# 8_bit_Left_Rev_A.net
KiCad netlist of a schematic drawn in EAGLE
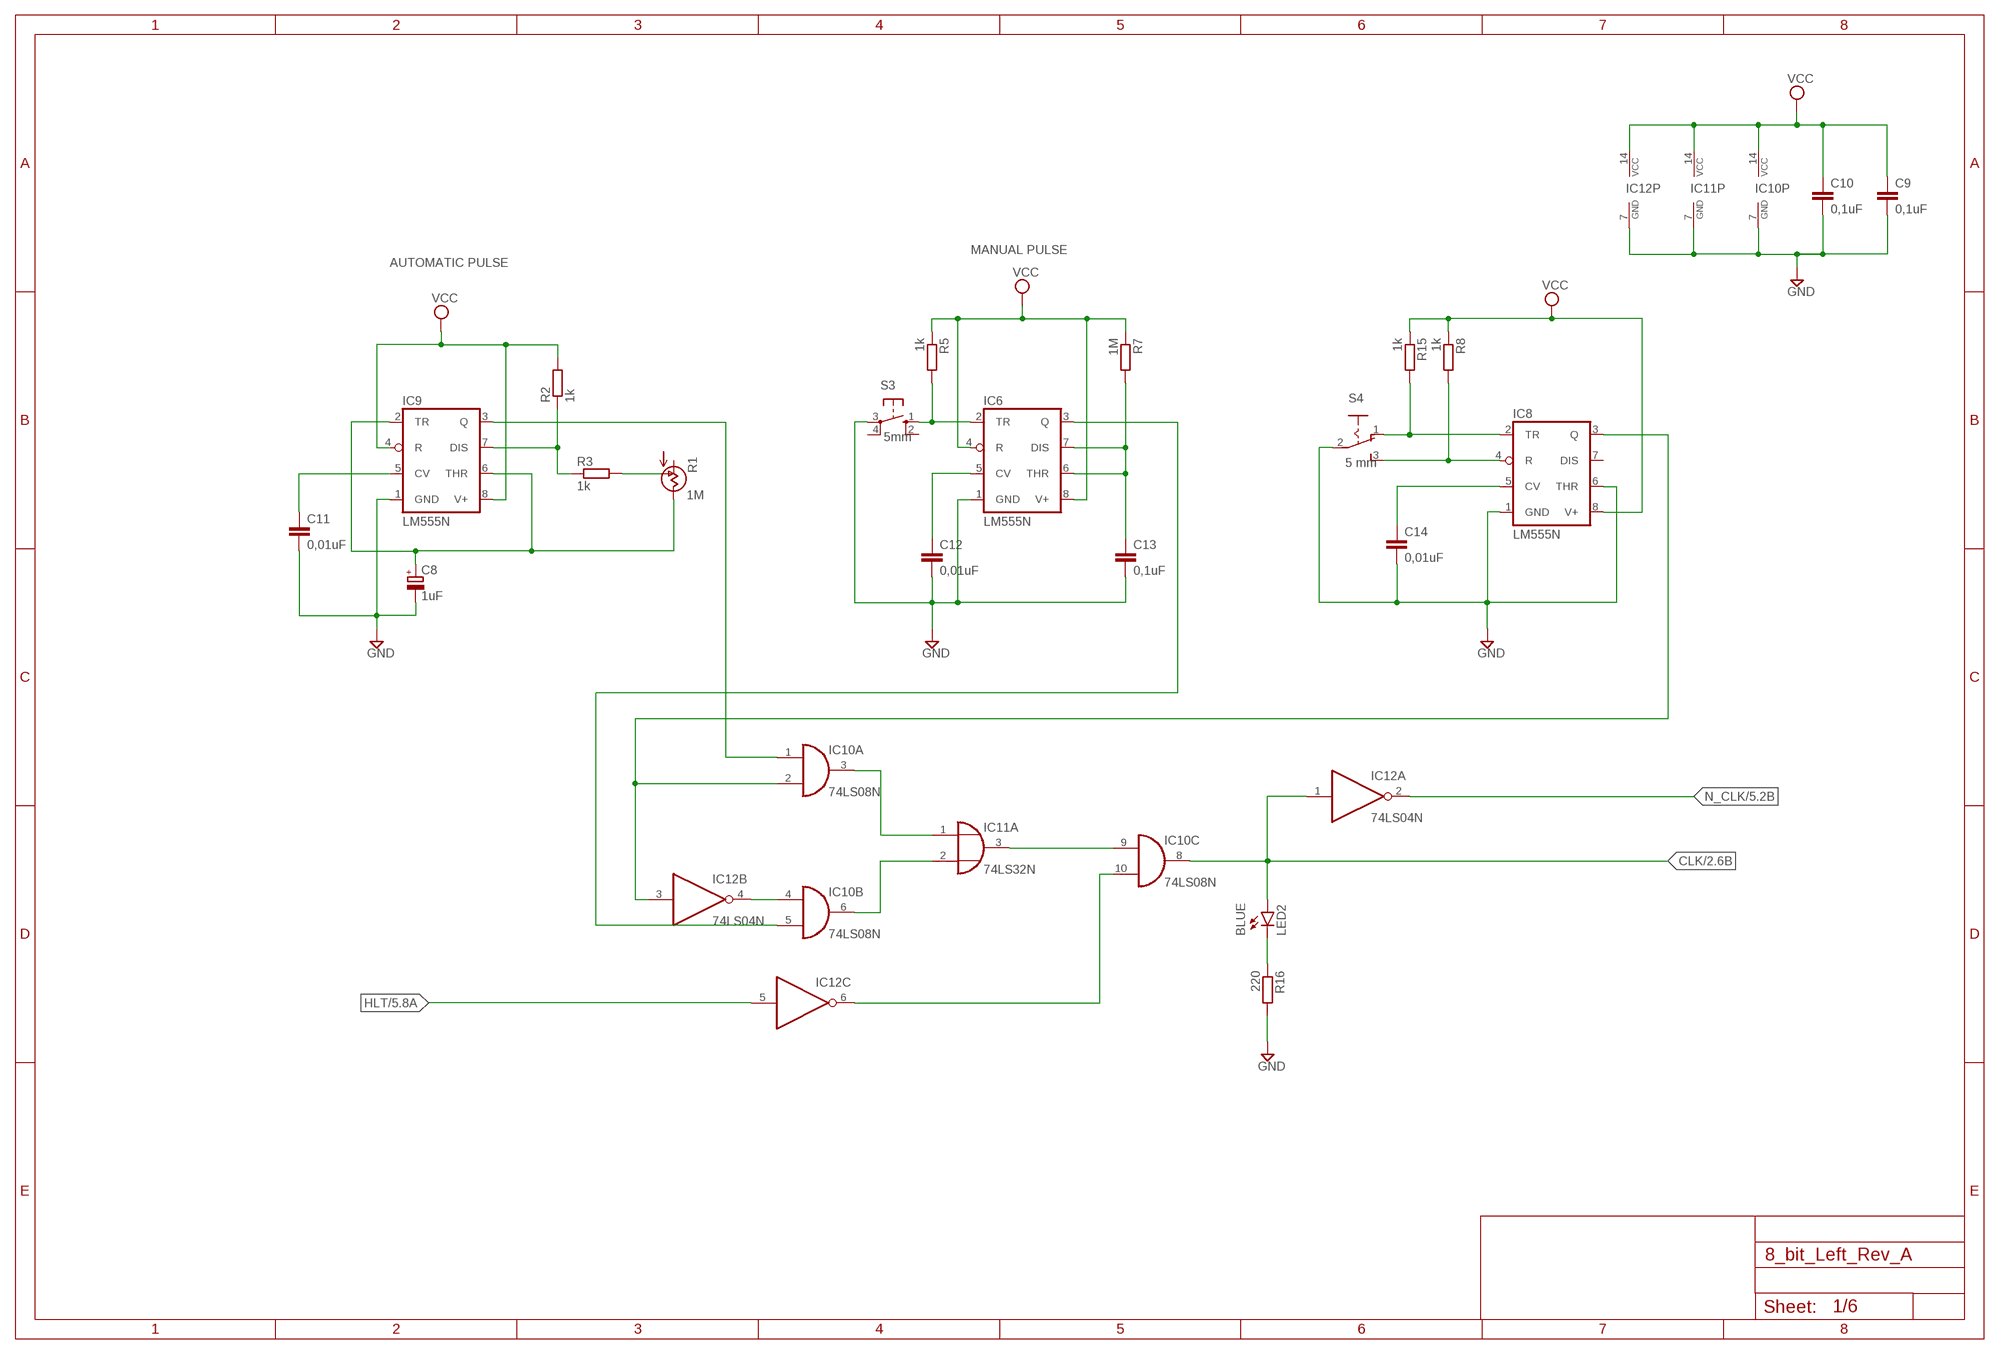
[diagram p0: schematic, sheet 1]
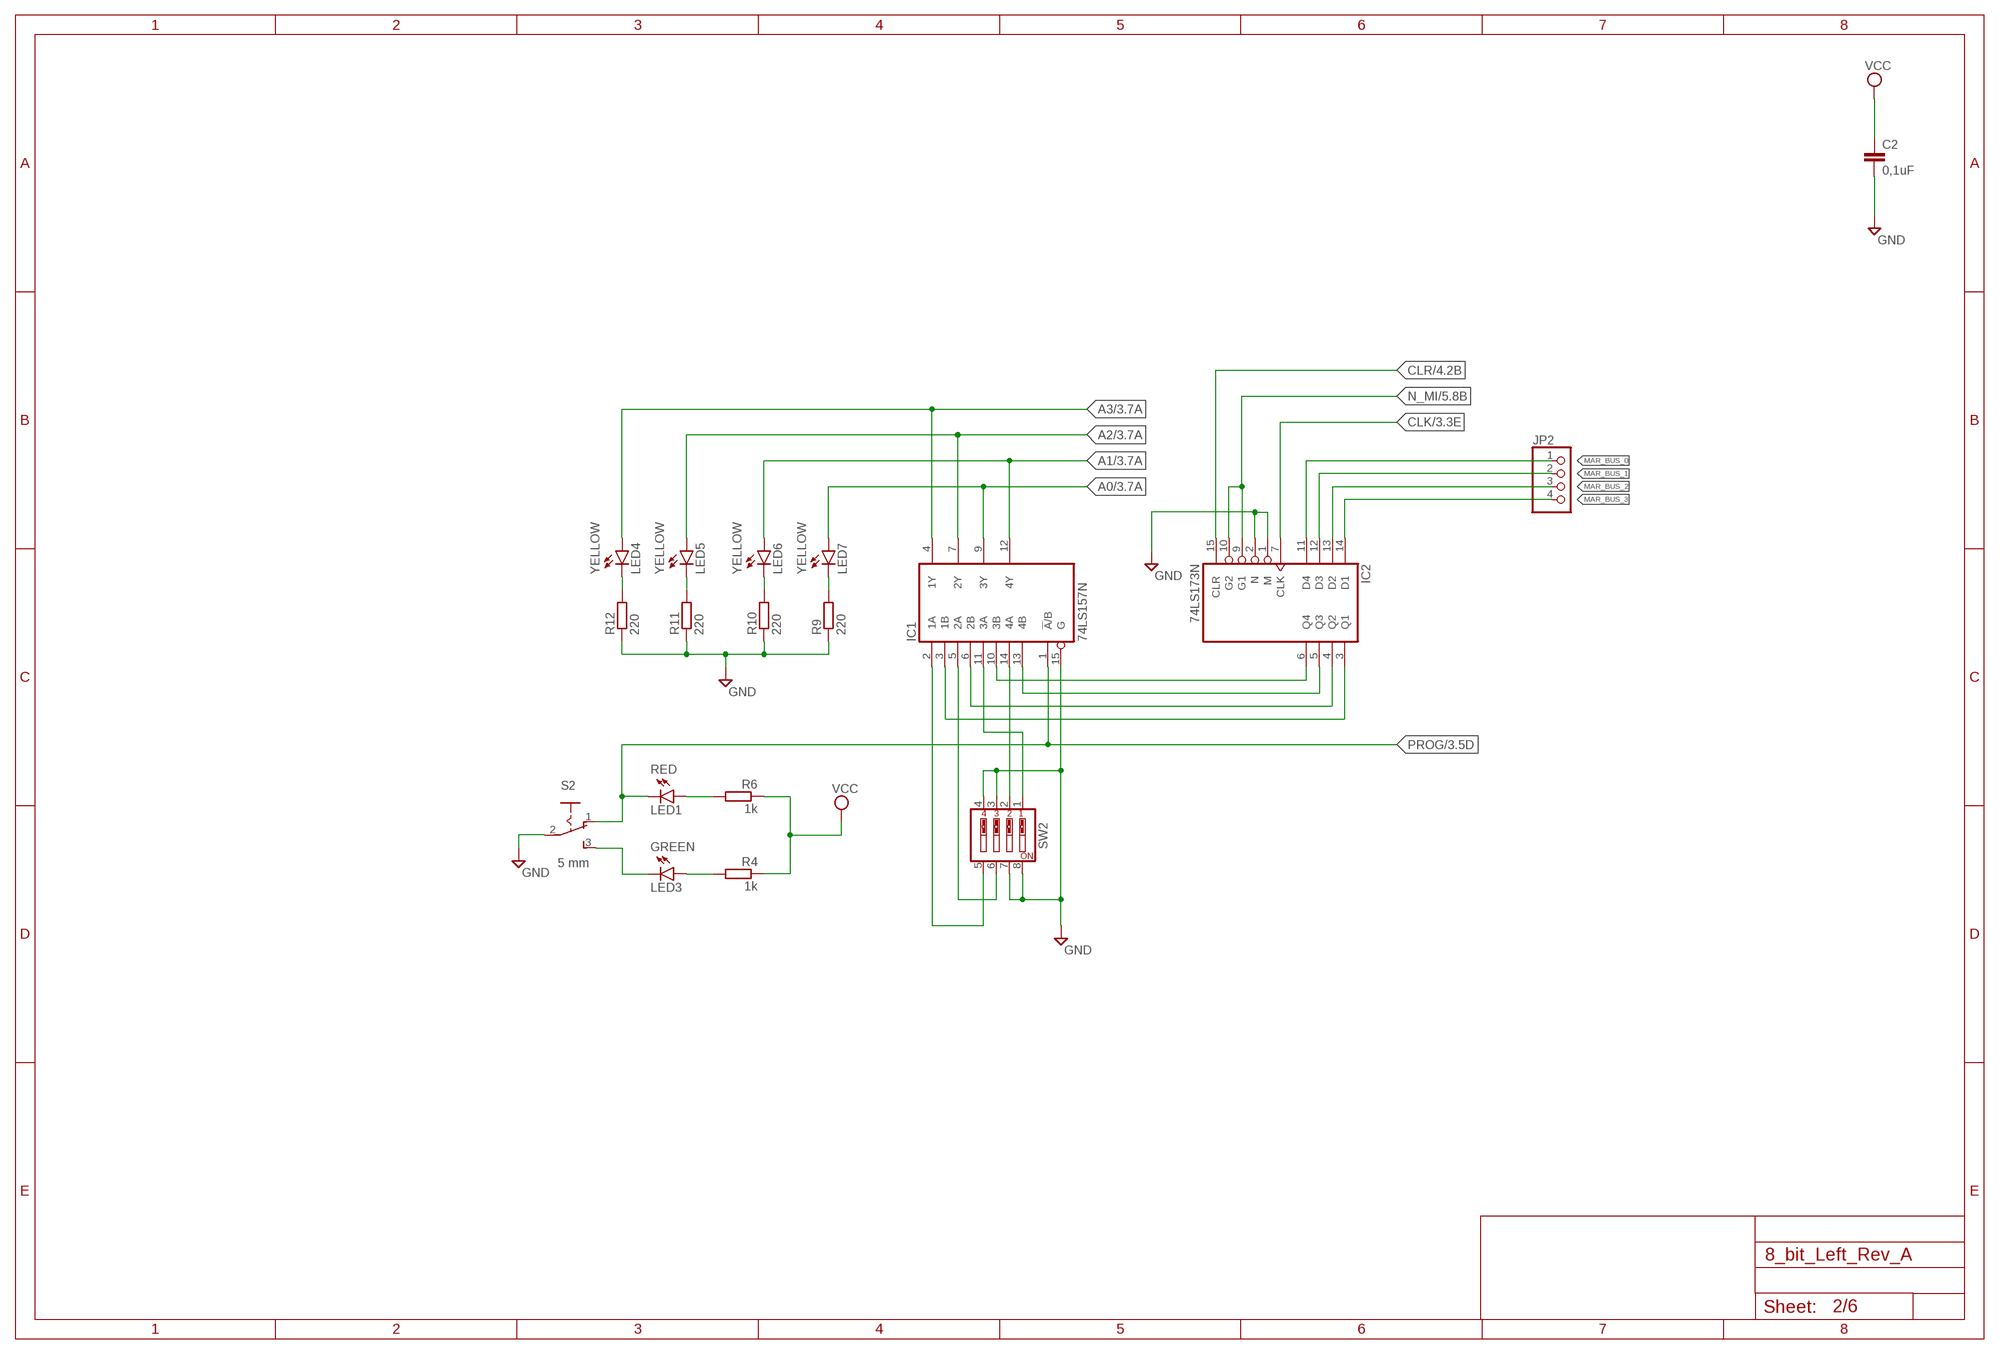
[diagram p1: schematic, sheet 2]
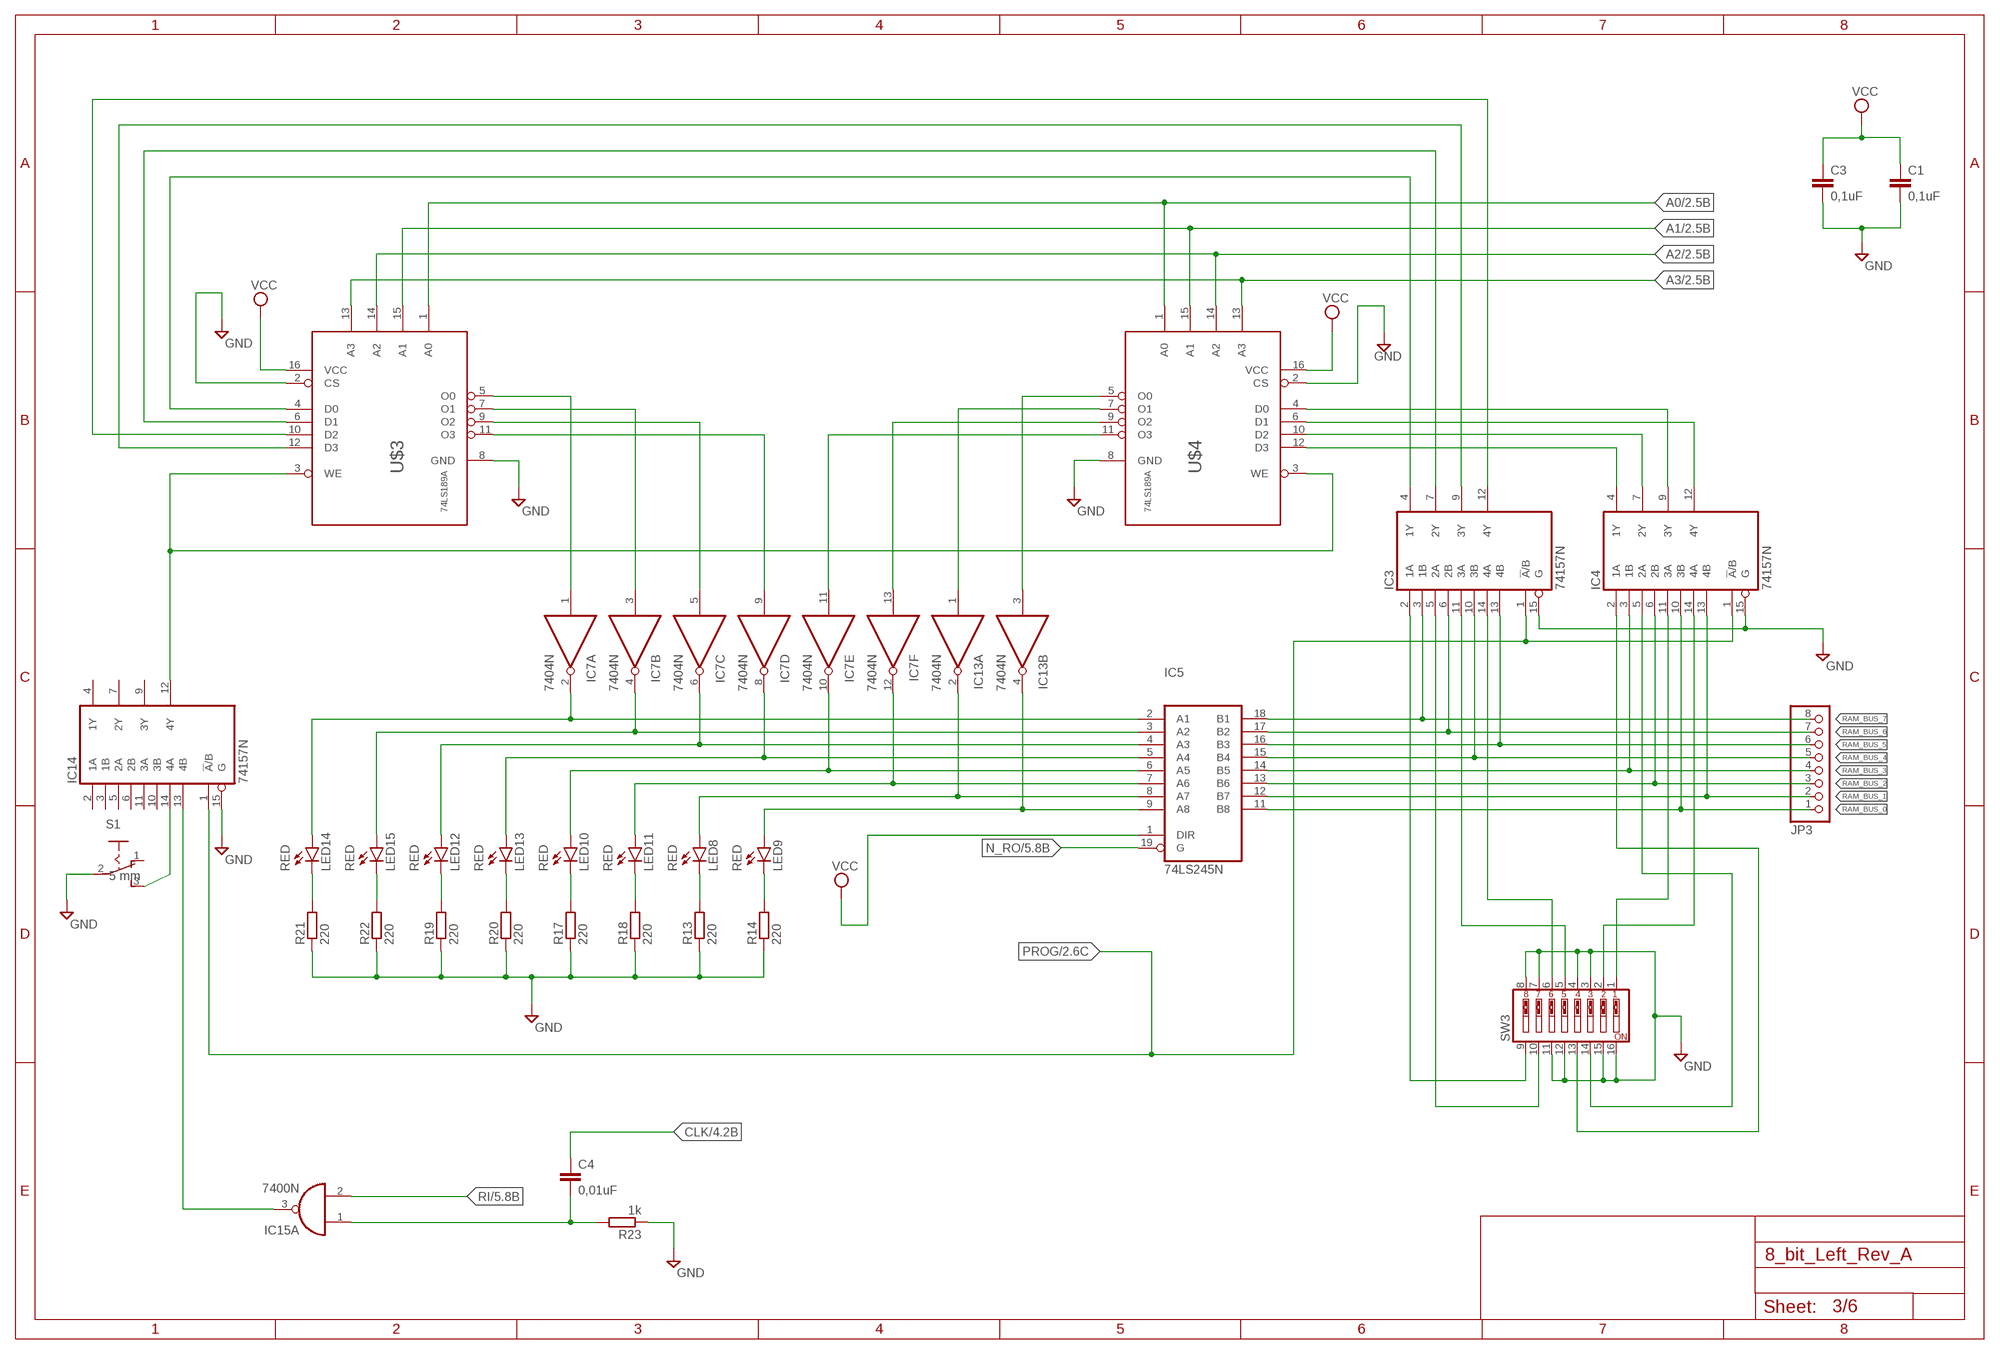
[diagram p2: schematic, sheet 3]
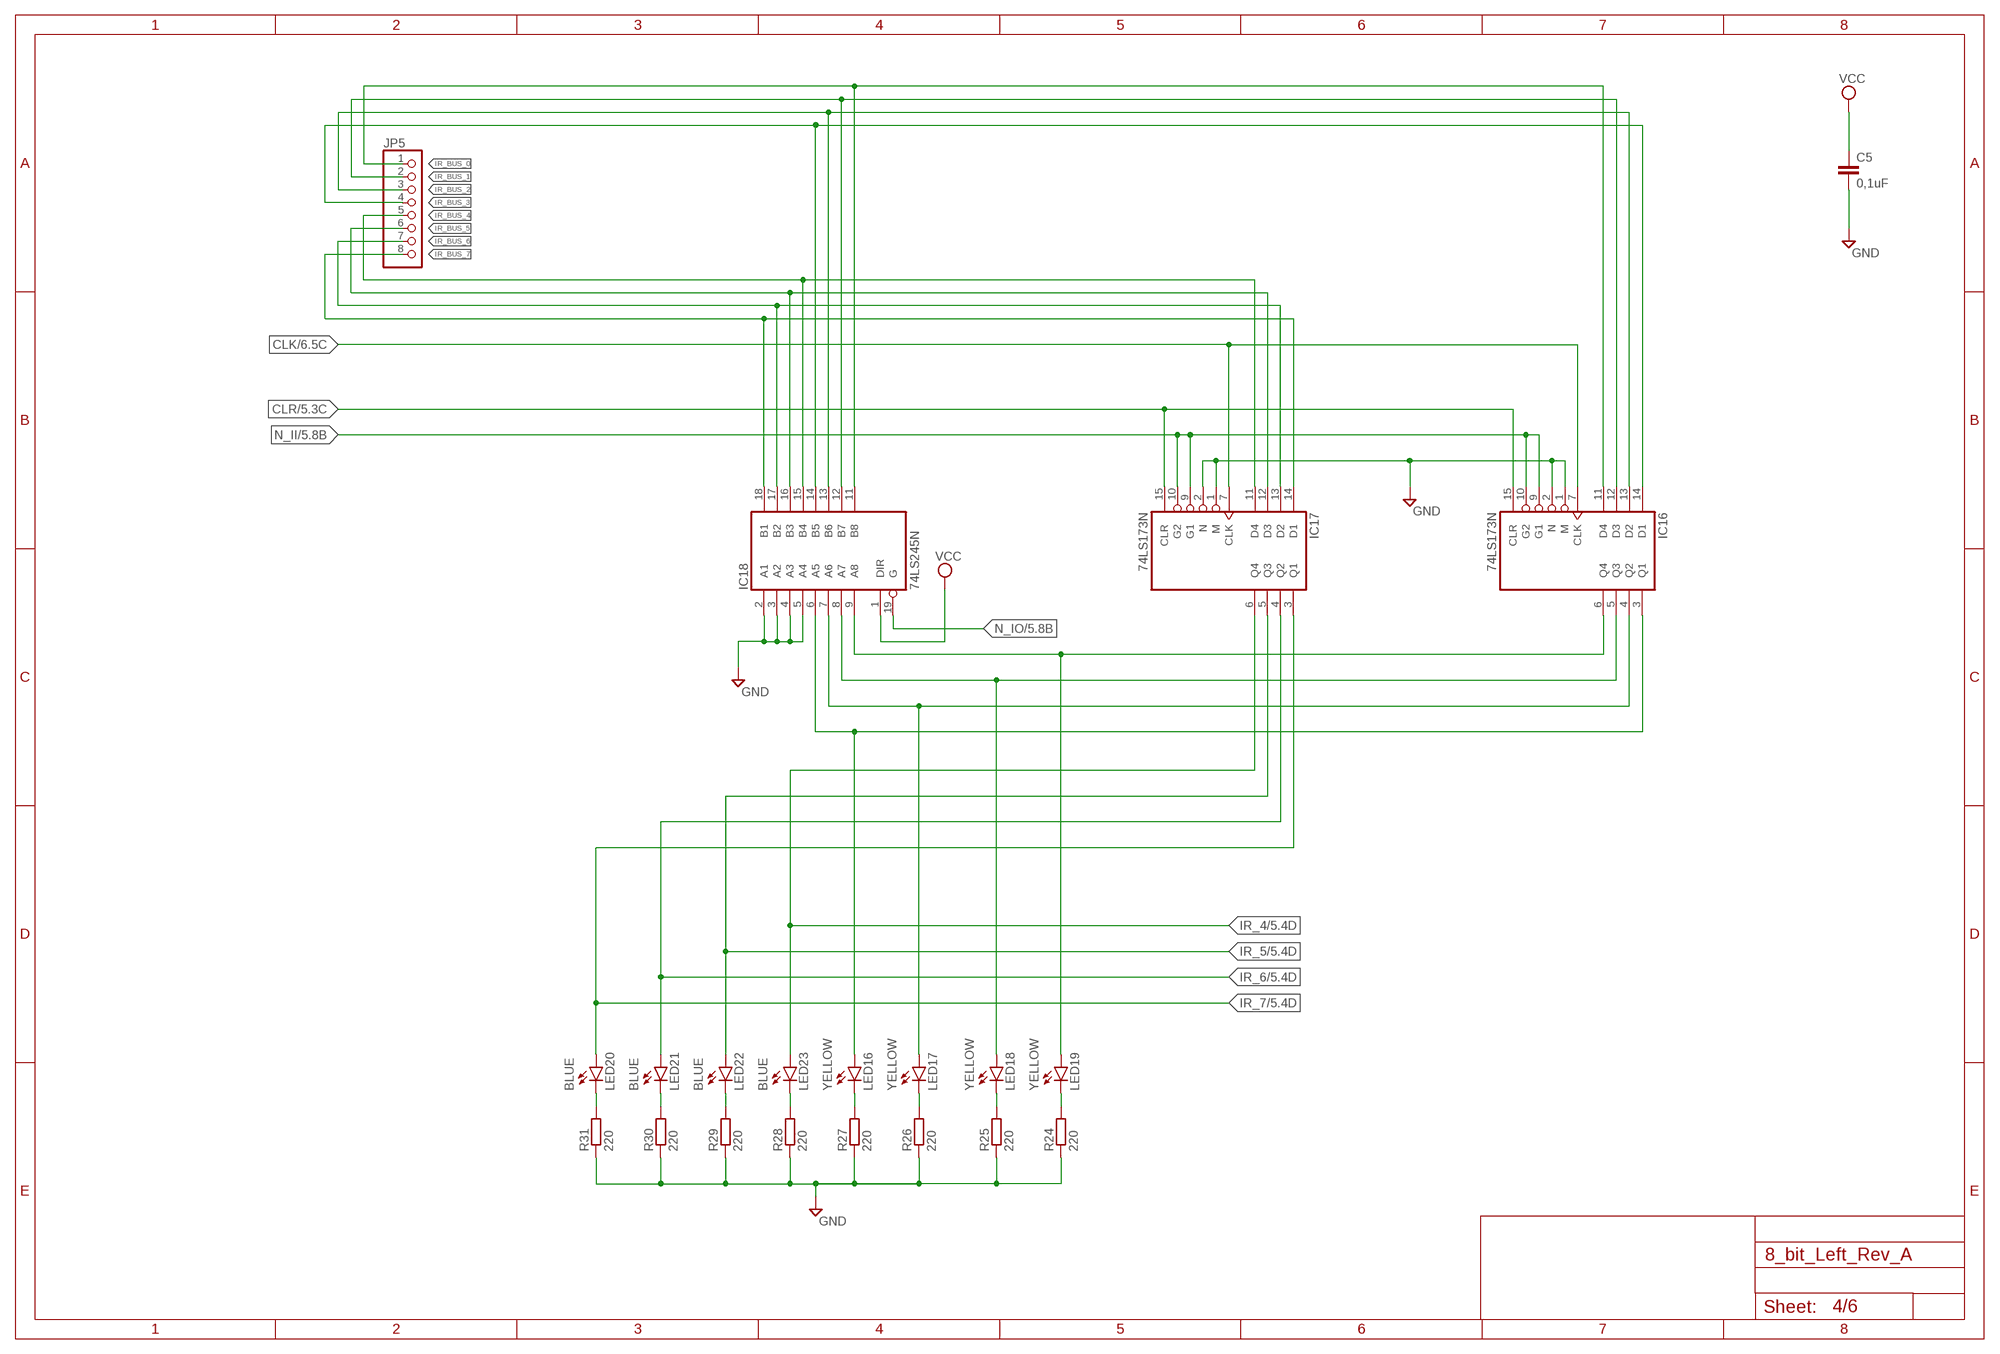
[diagram p3: schematic, sheet 4]
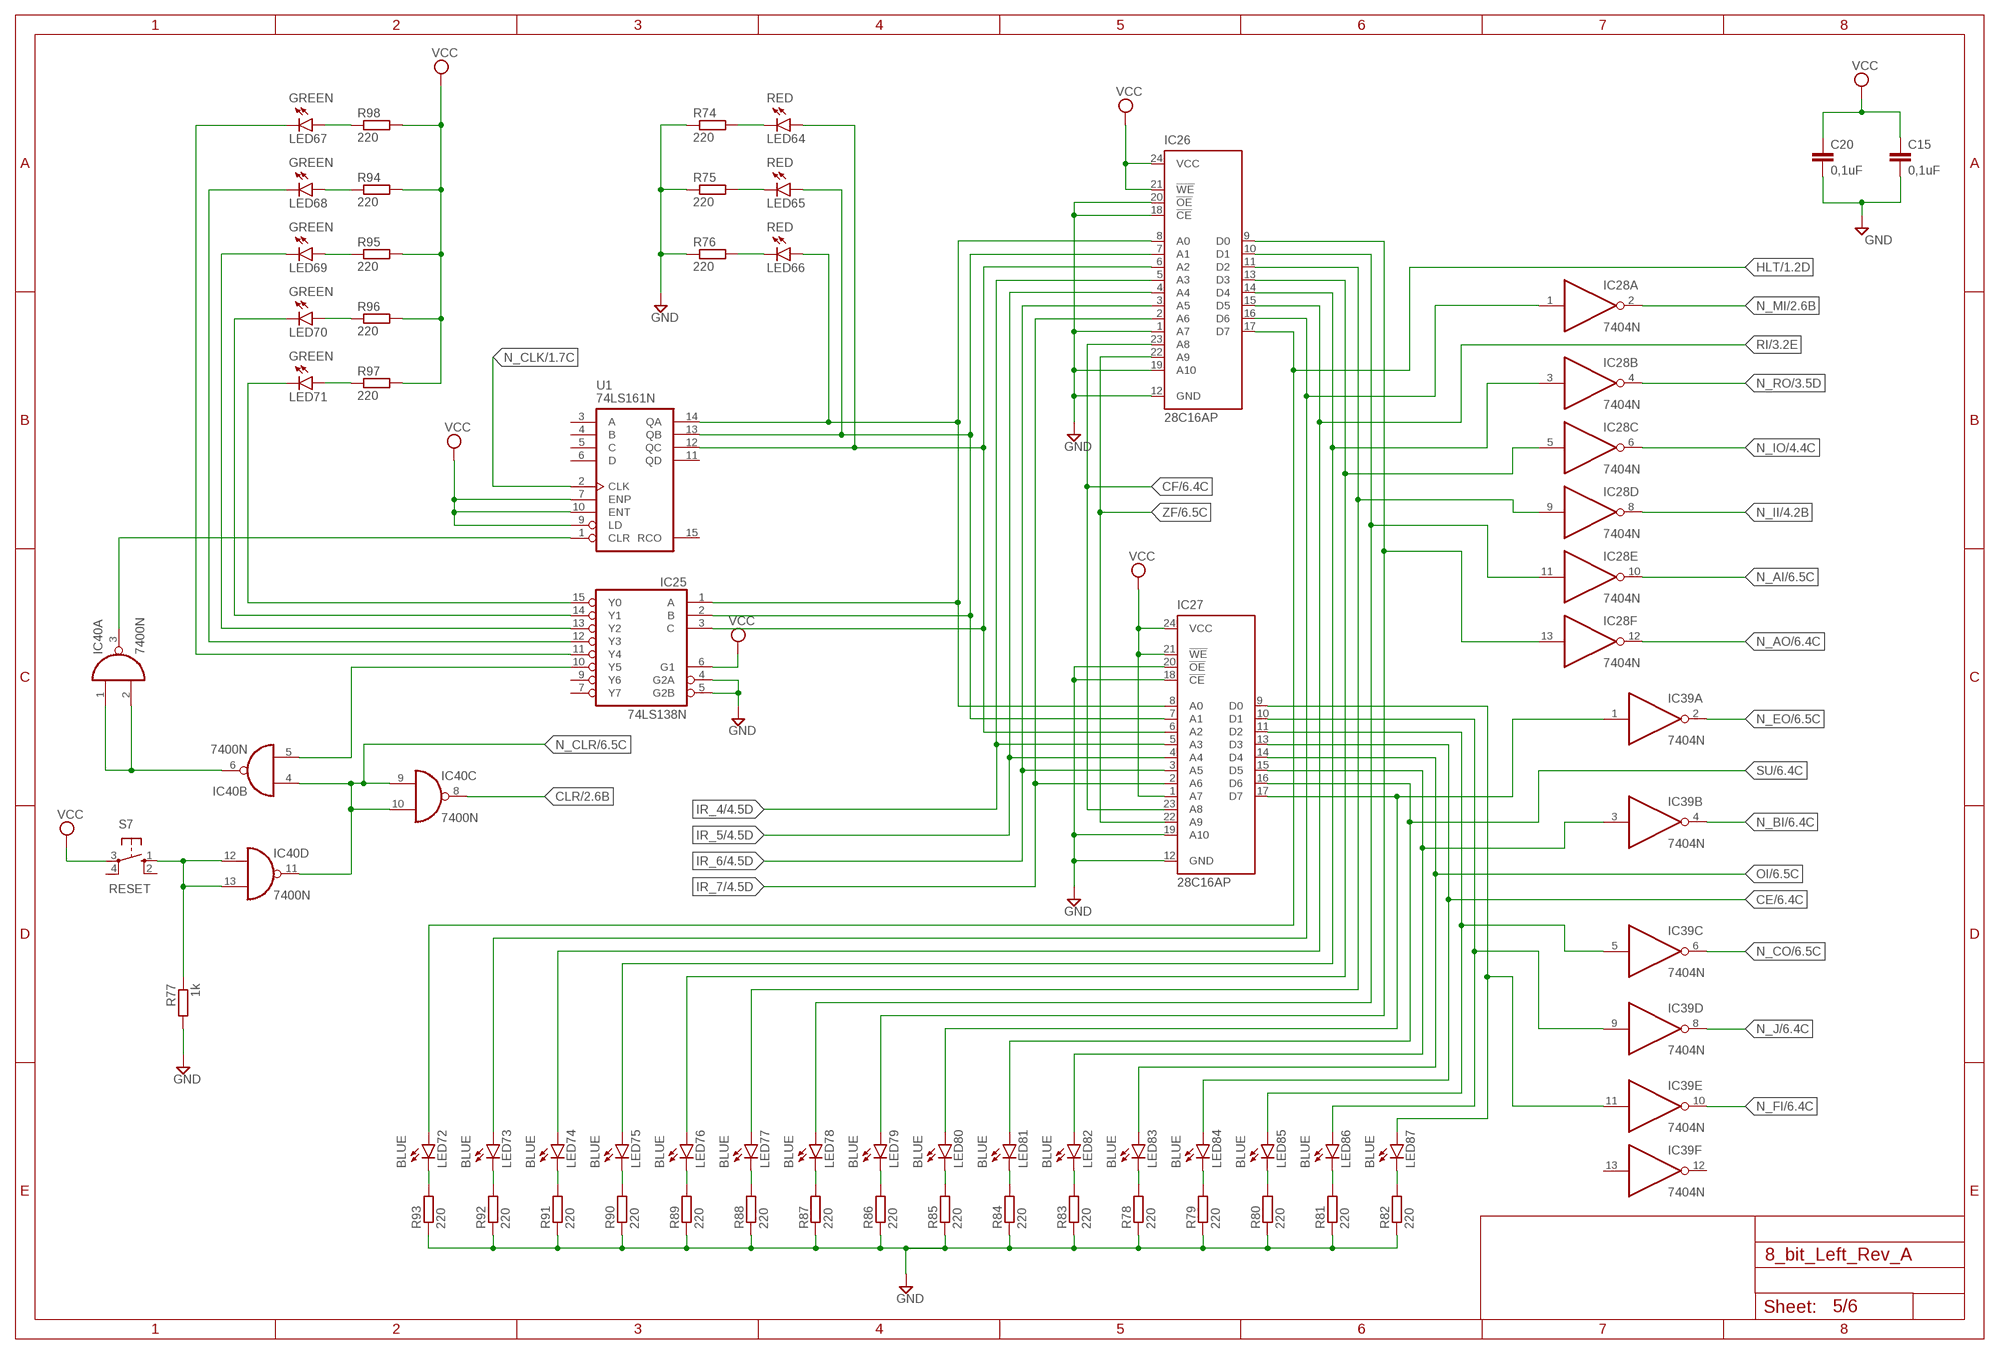
[diagram p4: schematic, sheet 5]
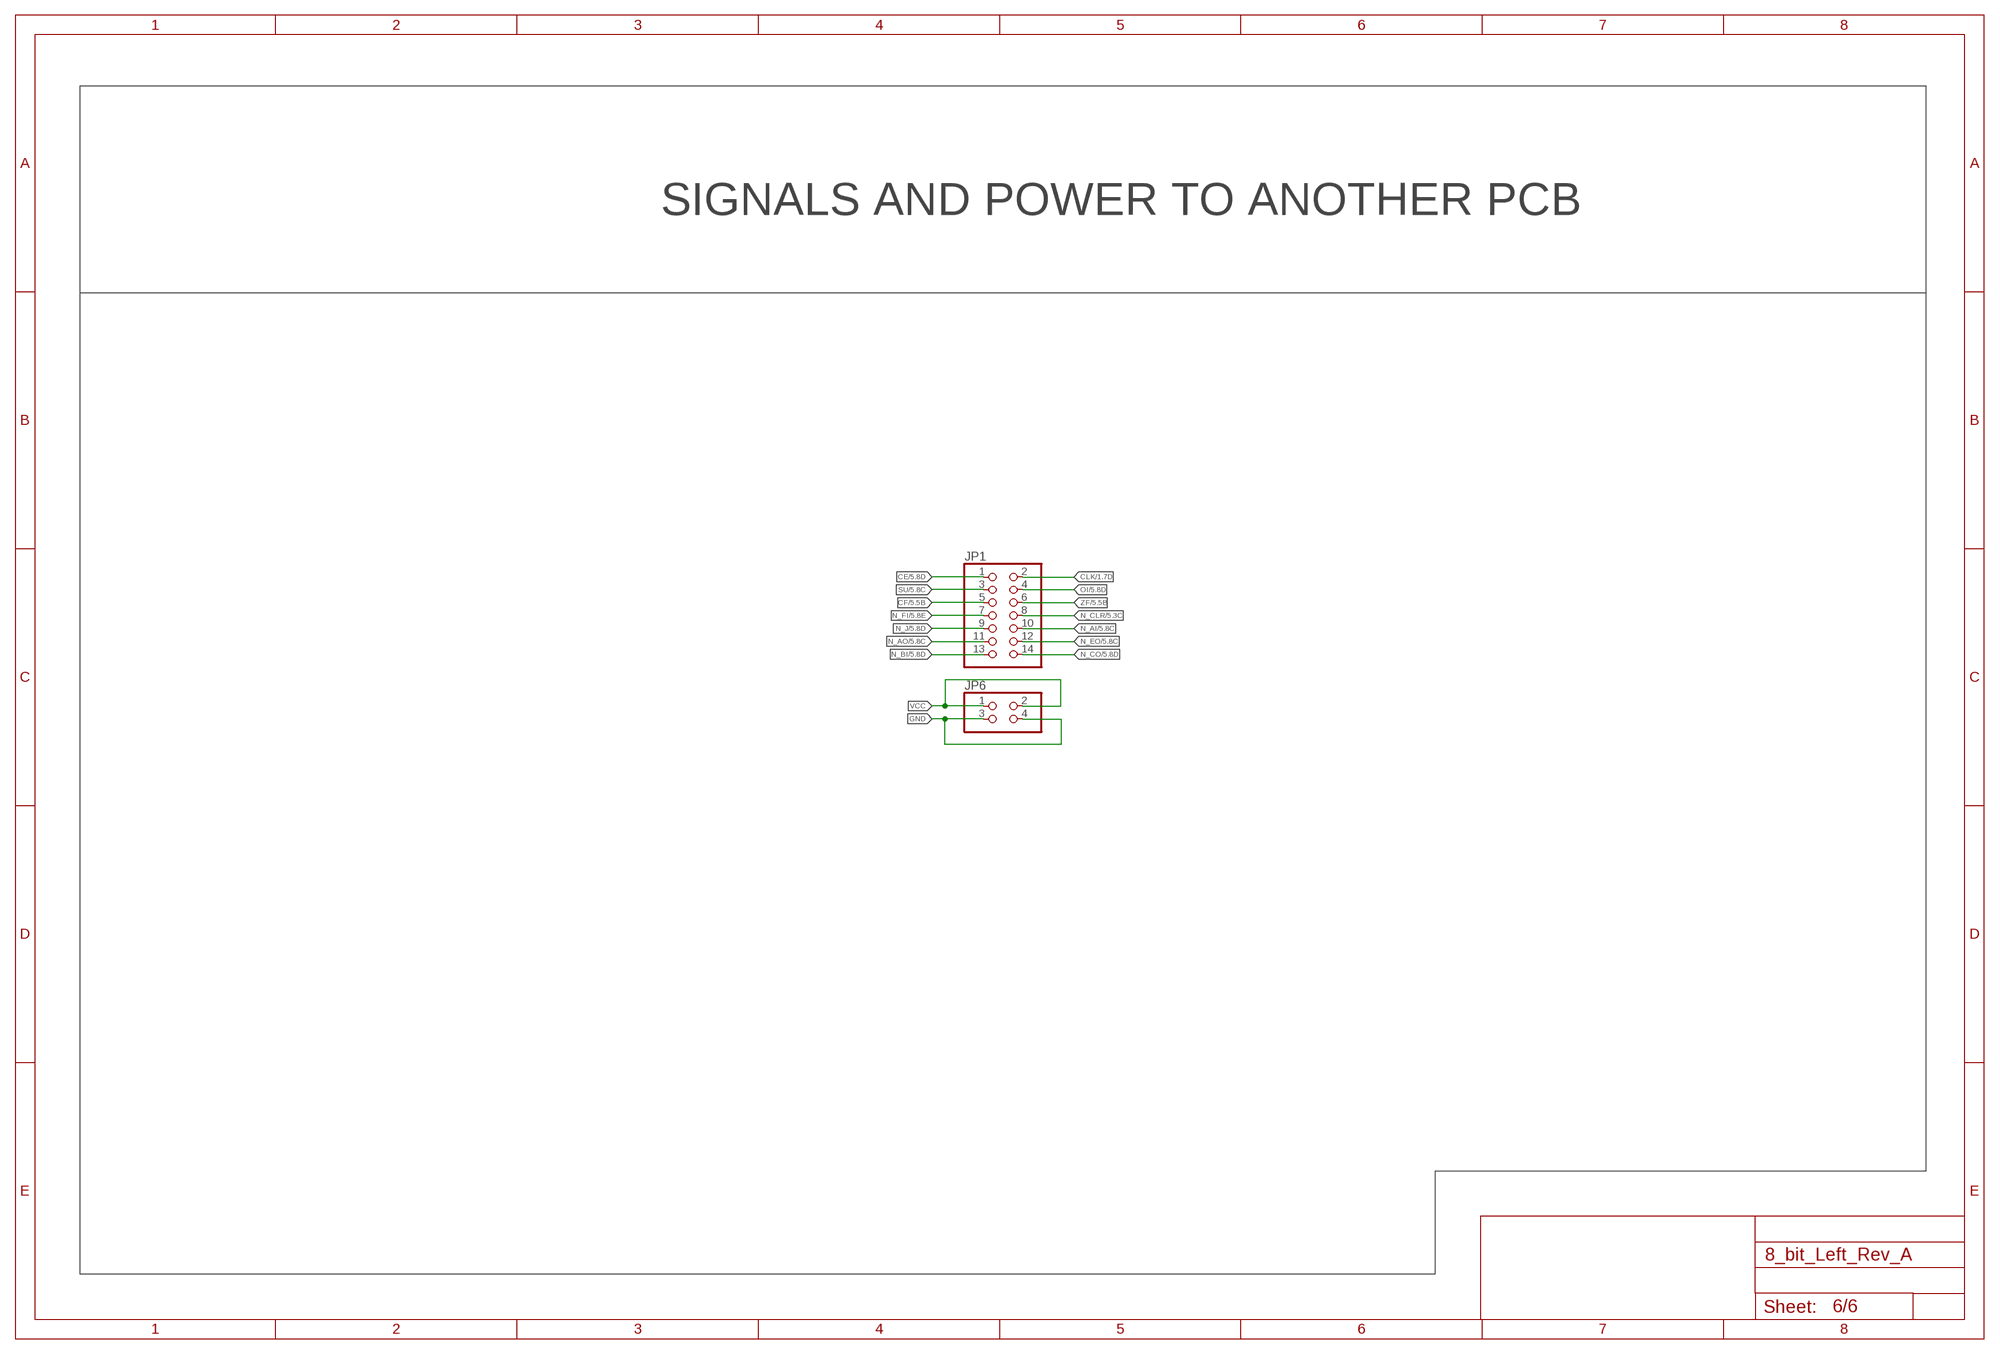
[diagram p5: schematic, sheet 6]

(export (version "E")
  (design (tool "Eeschema 10.0.6"))
  (components
    (comp (ref "C8")
      (value "1uF")
      (footprint "eagle-import:E2-5")
      (libsource (lib "eagle-import") (part "CPOL-EUE2-5"))
    )
    (comp (ref "C9")
      (value "0,1uF")
      (footprint "eagle-import:C025-030X050")
      (libsource (lib "eagle-import") (part "C-EU025-030X050"))
    )
    (comp (ref "C10")
      (value "0,1uF")
      (footprint "eagle-import:C025-030X050")
      (libsource (lib "eagle-import") (part "C-EU025-030X050"))
    )
    (comp (ref "C11")
      (value "0,01uF")
      (footprint "eagle-import:C025-030X050")
      (libsource (lib "eagle-import") (part "C-EU025-030X050"))
    )
    (comp (ref "C12")
      (value "0,01uF")
      (footprint "eagle-import:C025-030X050")
      (libsource (lib "eagle-import") (part "C-EU025-030X050"))
    )
    (comp (ref "C13")
      (value "0,1uF")
      (footprint "eagle-import:C025-030X050")
      (libsource (lib "eagle-import") (part "C-EU025-030X050"))
    )
    (comp (ref "C14")
      (value "0,01uF")
      (footprint "eagle-import:C025-030X050")
      (libsource (lib "eagle-import") (part "C-EU025-030X050"))
    )
    (comp (ref "IC6")
      (value "LM555N")
      (footprint "eagle-import:DIL08")
      (libsource (lib "eagle-import") (part "555NLM"))
    )
    (comp (ref "IC8")
      (value "LM555N")
      (footprint "eagle-import:DIL08")
      (libsource (lib "eagle-import") (part "555NLM"))
    )
    (comp (ref "IC9")
      (value "LM555N")
      (footprint "eagle-import:DIL08")
      (libsource (lib "eagle-import") (part "555NLM"))
    )
    (comp (ref "IC10")
      (value "74LS08N")
      (footprint "eagle-import:DIL14")
      (libsource (lib "eagle-import") (part "7408NLS"))
    )
    (comp (ref "IC11")
      (value "74LS32N")
      (footprint "eagle-import:DIL14")
      (libsource (lib "eagle-import") (part "7432NLS"))
    )
    (comp (ref "IC12")
      (value "74LS04N")
      (footprint "eagle-import:DIL14")
      (libsource (lib "eagle-import") (part "7404NLS"))
    )
    (comp (ref "LED2")
      (value "BLUE")
      (footprint "eagle-import:LED5MM")
      (libsource (lib "eagle-import") (part "LED5MM"))
    )
    (comp (ref "R1")
      (value "1M")
      (footprint "eagle-import:S64W")
      (fields (field (name "R9") "1M"))
      (libsource (lib "eagle-import") (part "POTTRS64W"))
    )
    (comp (ref "R2")
      (value "1k")
      (footprint "eagle-import:0207_10")
      (libsource (lib "eagle-import") (part "R-EU_0207/10"))
    )
    (comp (ref "R3")
      (value "1k")
      (footprint "eagle-import:0207_10")
      (libsource (lib "eagle-import") (part "R-EU_0207/10"))
    )
    (comp (ref "R5")
      (value "1k")
      (footprint "eagle-import:0207_10")
      (libsource (lib "eagle-import") (part "R-EU_0207/10"))
    )
    (comp (ref "R7")
      (value "1M")
      (footprint "eagle-import:0207_10")
      (libsource (lib "eagle-import") (part "R-EU_0207/10"))
    )
    (comp (ref "R8")
      (value "1k")
      (footprint "eagle-import:0207_10")
      (libsource (lib "eagle-import") (part "R-EU_0207/10"))
    )
    (comp (ref "R15")
      (value "1k")
      (footprint "eagle-import:0207_10")
      (libsource (lib "eagle-import") (part "R-EU_0207/10"))
    )
    (comp (ref "R16")
      (value "220")
      (footprint "eagle-import:0207_10")
      (libsource (lib "eagle-import") (part "R-EU_0207/10"))
    )
    (comp (ref "S3")
      (value "5mm")
      (footprint "eagle-import:B3F-10XX")
      (fields (field (name "MPN") "B3F-1000"))
      (libsource (lib "eagle-import") (part "10-XX"))
    )
    (comp (ref "S4")
      (value "5 mm")
      (footprint "eagle-import:255SB")
      (libsource (lib "eagle-import") (part "255SB"))
    )
    (comp (ref "C1")
      (value "0,1uF")
      (footprint "eagle-import:C025-030X050")
      (libsource (lib "eagle-import") (part "C-EU025-030X050"))
    )
    (comp (ref "C3")
      (value "0,1uF")
      (footprint "eagle-import:C025-030X050")
      (libsource (lib "eagle-import") (part "C-EU025-030X050"))
    )
    (comp (ref "C4")
      (value "0,01uF")
      (footprint "eagle-import:C025-030X050")
      (libsource (lib "eagle-import") (part "C-EU025-030X050"))
    )
    (comp (ref "IC3")
      (value "74157N")
      (footprint "eagle-import:DIL16")
      (libsource (lib "eagle-import") (part "74xx-eu_85_74157N"))
    )
    (comp (ref "IC4")
      (value "74157N")
      (footprint "eagle-import:DIL16")
      (libsource (lib "eagle-import") (part "74xx-eu_85_74157N"))
    )
    (comp (ref "IC5")
      (value "74LS245N")
      (footprint "eagle-import:DIL20")
      (libsource (lib "eagle-import") (part "74245NLS"))
    )
    (comp (ref "IC7")
      (value "7404N")
      (footprint "eagle-import:DIL14")
      (libsource (lib "eagle-import") (part "7404N"))
    )
    (comp (ref "IC13")
      (value "7404N")
      (footprint "eagle-import:DIL14")
      (libsource (lib "eagle-import") (part "7404N"))
    )
    (comp (ref "IC14")
      (value "74157N")
      (footprint "eagle-import:DIL16")
      (libsource (lib "eagle-import") (part "74xx-eu_85_74157N"))
    )
    (comp (ref "IC15")
      (value "7400N")
      (footprint "eagle-import:DIL14")
      (libsource (lib "eagle-import") (part "7400N"))
    )
    (comp (ref "JP3")
      (value "PINHD-1X8")
      (footprint "eagle-import:1X08")
      (libsource (lib "eagle-import") (part "PINHD-1X8"))
    )
    (comp (ref "LED8")
      (value "RED")
      (footprint "eagle-import:LED5MM")
      (libsource (lib "eagle-import") (part "LED5MM"))
    )
    (comp (ref "LED9")
      (value "RED")
      (footprint "eagle-import:LED5MM")
      (libsource (lib "eagle-import") (part "LED5MM"))
    )
    (comp (ref "LED10")
      (value "RED")
      (footprint "eagle-import:LED5MM")
      (libsource (lib "eagle-import") (part "LED5MM"))
    )
    (comp (ref "LED11")
      (value "RED")
      (footprint "eagle-import:LED5MM")
      (libsource (lib "eagle-import") (part "LED5MM"))
    )
    (comp (ref "LED12")
      (value "RED")
      (footprint "eagle-import:LED5MM")
      (libsource (lib "eagle-import") (part "LED5MM"))
    )
    (comp (ref "LED13")
      (value "RED")
      (footprint "eagle-import:LED5MM")
      (libsource (lib "eagle-import") (part "LED5MM"))
    )
    (comp (ref "LED14")
      (value "RED")
      (footprint "eagle-import:LED5MM")
      (libsource (lib "eagle-import") (part "LED5MM"))
    )
    (comp (ref "LED15")
      (value "RED")
      (footprint "eagle-import:LED5MM")
      (libsource (lib "eagle-import") (part "LED5MM"))
    )
    (comp (ref "R13")
      (value "220")
      (footprint "eagle-import:0207_10")
      (libsource (lib "eagle-import") (part "R-EU_0207/10"))
    )
    (comp (ref "R14")
      (value "220")
      (footprint "eagle-import:0207_10")
      (libsource (lib "eagle-import") (part "R-EU_0207/10"))
    )
    (comp (ref "R17")
      (value "220")
      (footprint "eagle-import:0207_10")
      (libsource (lib "eagle-import") (part "R-EU_0207/10"))
    )
    (comp (ref "R18")
      (value "220")
      (footprint "eagle-import:0207_10")
      (libsource (lib "eagle-import") (part "R-EU_0207/10"))
    )
    (comp (ref "R19")
      (value "220")
      (footprint "eagle-import:0207_10")
      (libsource (lib "eagle-import") (part "R-EU_0207/10"))
    )
    (comp (ref "R20")
      (value "220")
      (footprint "eagle-import:0207_10")
      (libsource (lib "eagle-import") (part "R-EU_0207/10"))
    )
    (comp (ref "R21")
      (value "220")
      (footprint "eagle-import:0207_10")
      (libsource (lib "eagle-import") (part "R-EU_0207/10"))
    )
    (comp (ref "R22")
      (value "220")
      (footprint "eagle-import:0207_10")
      (libsource (lib "eagle-import") (part "R-EU_0207/10"))
    )
    (comp (ref "R23")
      (value "1k")
      (footprint "eagle-import:0207_10")
      (libsource (lib "eagle-import") (part "R-EU_0207/10"))
    )
    (comp (ref "S1")
      (value "5 mm")
      (footprint "eagle-import:255SB")
      (libsource (lib "eagle-import") (part "255SB"))
    )
    (comp (ref "SW3")
      (value "SW_DIP-8")
      (footprint "eagle-import:EDG-08")
      (libsource (lib "eagle-import") (part "SW_DIP-8"))
    )
    (comp (ref "U$3")
      (value "74LS189A")
      (footprint "eagle-import:74LS189")
      (libsource (lib "eagle-import") (part "74LS189A"))
    )
    (comp (ref "U$4")
      (value "74LS189A")
      (footprint "eagle-import:74LS189")
      (libsource (lib "eagle-import") (part "74LS189A"))
    )
    (comp (ref "C2")
      (value "0,1uF")
      (footprint "eagle-import:C025-030X050")
      (libsource (lib "eagle-import") (part "C-EU025-030X050"))
    )
    (comp (ref "IC1")
      (value "74LS157N")
      (footprint "eagle-import:DIL16")
      (libsource (lib "eagle-import") (part "74157NLS"))
    )
    (comp (ref "IC2")
      (value "74LS173N")
      (footprint "eagle-import:DIL16")
      (libsource (lib "eagle-import") (part "74173NLS"))
    )
    (comp (ref "JP2")
      (value "PINHD-1X4")
      (footprint "eagle-import:1X04")
      (libsource (lib "eagle-import") (part "PINHD-1X4"))
    )
    (comp (ref "LED1")
      (value "RED")
      (footprint "eagle-import:LED5MM")
      (libsource (lib "eagle-import") (part "LED5MM"))
    )
    (comp (ref "LED3")
      (value "GREEN")
      (footprint "eagle-import:LED5MM")
      (libsource (lib "eagle-import") (part "LED5MM"))
    )
    (comp (ref "LED4")
      (value "YELLOW")
      (footprint "eagle-import:LED5MM")
      (libsource (lib "eagle-import") (part "LED5MM"))
    )
    (comp (ref "LED5")
      (value "YELLOW")
      (footprint "eagle-import:LED5MM")
      (libsource (lib "eagle-import") (part "LED5MM"))
    )
    (comp (ref "LED6")
      (value "YELLOW")
      (footprint "eagle-import:LED5MM")
      (libsource (lib "eagle-import") (part "LED5MM"))
    )
    (comp (ref "LED7")
      (value "YELLOW")
      (footprint "eagle-import:LED5MM")
      (libsource (lib "eagle-import") (part "LED5MM"))
    )
    (comp (ref "R4")
      (value "1k")
      (footprint "eagle-import:0207_10")
      (libsource (lib "eagle-import") (part "R-EU_0207/10"))
    )
    (comp (ref "R6")
      (value "1k")
      (footprint "eagle-import:0207_10")
      (libsource (lib "eagle-import") (part "R-EU_0207/10"))
    )
    (comp (ref "R9")
      (value "220")
      (footprint "eagle-import:0207_10")
      (libsource (lib "eagle-import") (part "R-EU_0207/10"))
    )
    (comp (ref "R10")
      (value "220")
      (footprint "eagle-import:0207_10")
      (libsource (lib "eagle-import") (part "R-EU_0207/10"))
    )
    (comp (ref "R11")
      (value "220")
      (footprint "eagle-import:0207_10")
      (libsource (lib "eagle-import") (part "R-EU_0207/10"))
    )
    (comp (ref "R12")
      (value "220")
      (footprint "eagle-import:0207_10")
      (libsource (lib "eagle-import") (part "R-EU_0207/10"))
    )
    (comp (ref "S2")
      (value "5 mm")
      (footprint "eagle-import:255SB")
      (libsource (lib "eagle-import") (part "255SB"))
    )
    (comp (ref "SW2")
      (value "SW_DIP-4")
      (footprint "eagle-import:EDG-04")
      (libsource (lib "eagle-import") (part "SW_DIP-4"))
    )
    (comp (ref "C15")
      (value "0,1uF")
      (footprint "eagle-import:C025-030X050")
      (libsource (lib "eagle-import") (part "C-EU025-030X050"))
    )
    (comp (ref "C20")
      (value "0,1uF")
      (footprint "eagle-import:C025-030X050")
      (libsource (lib "eagle-import") (part "C-EU025-030X050"))
    )
    (comp (ref "IC25")
      (value "74LS138N")
      (footprint "eagle-import:DIL16")
      (libsource (lib "eagle-import") (part "74138NLS"))
    )
    (comp (ref "IC26")
      (value "28C16AP")
      (footprint "eagle-import:DIL24-6")
      (fields (field (name "MPN") "CAT28C16ALI-12"))
      (libsource (lib "eagle-import") (part "2816APC"))
    )
    (comp (ref "IC27")
      (value "28C16AP")
      (footprint "eagle-import:DIL24-6")
      (fields (field (name "MPN") "CAT28C16ALI-12"))
      (libsource (lib "eagle-import") (part "2816APC"))
    )
    (comp (ref "IC28")
      (value "7404N")
      (footprint "eagle-import:DIL14")
      (libsource (lib "eagle-import") (part "7404N"))
    )
    (comp (ref "IC39")
      (value "7404N")
      (footprint "eagle-import:DIL14")
      (libsource (lib "eagle-import") (part "7404N"))
    )
    (comp (ref "IC40")
      (value "7400N")
      (footprint "eagle-import:DIL14")
      (libsource (lib "eagle-import") (part "7400N"))
    )
    (comp (ref "LED64")
      (value "RED")
      (footprint "eagle-import:LED5MM")
      (libsource (lib "eagle-import") (part "LED5MM"))
    )
    (comp (ref "LED65")
      (value "RED")
      (footprint "eagle-import:LED5MM")
      (libsource (lib "eagle-import") (part "LED5MM"))
    )
    (comp (ref "LED66")
      (value "RED")
      (footprint "eagle-import:LED5MM")
      (libsource (lib "eagle-import") (part "LED5MM"))
    )
    (comp (ref "LED67")
      (value "GREEN")
      (footprint "eagle-import:LED5MM")
      (libsource (lib "eagle-import") (part "LED5MM"))
    )
    (comp (ref "LED68")
      (value "GREEN")
      (footprint "eagle-import:LED5MM")
      (libsource (lib "eagle-import") (part "LED5MM"))
    )
    (comp (ref "LED69")
      (value "GREEN")
      (footprint "eagle-import:LED5MM")
      (libsource (lib "eagle-import") (part "LED5MM"))
    )
    (comp (ref "LED70")
      (value "GREEN")
      (footprint "eagle-import:LED5MM")
      (libsource (lib "eagle-import") (part "LED5MM"))
    )
    (comp (ref "LED71")
      (value "GREEN")
      (footprint "eagle-import:LED5MM")
      (libsource (lib "eagle-import") (part "LED5MM"))
    )
    (comp (ref "LED72")
      (value "BLUE")
      (footprint "eagle-import:LED5MM")
      (libsource (lib "eagle-import") (part "LED5MM"))
    )
    (comp (ref "LED73")
      (value "BLUE")
      (footprint "eagle-import:LED5MM")
      (libsource (lib "eagle-import") (part "LED5MM"))
    )
    (comp (ref "LED74")
      (value "BLUE")
      (footprint "eagle-import:LED5MM")
      (libsource (lib "eagle-import") (part "LED5MM"))
    )
    (comp (ref "LED75")
      (value "BLUE")
      (footprint "eagle-import:LED5MM")
      (libsource (lib "eagle-import") (part "LED5MM"))
    )
    (comp (ref "LED76")
      (value "BLUE")
      (footprint "eagle-import:LED5MM")
      (libsource (lib "eagle-import") (part "LED5MM"))
    )
    (comp (ref "LED77")
      (value "BLUE")
      (footprint "eagle-import:LED5MM")
      (libsource (lib "eagle-import") (part "LED5MM"))
    )
    (comp (ref "LED78")
      (value "BLUE")
      (footprint "eagle-import:LED5MM")
      (libsource (lib "eagle-import") (part "LED5MM"))
    )
    (comp (ref "LED79")
      (value "BLUE")
      (footprint "eagle-import:LED5MM")
      (libsource (lib "eagle-import") (part "LED5MM"))
    )
    (comp (ref "LED80")
      (value "BLUE")
      (footprint "eagle-import:LED5MM")
      (libsource (lib "eagle-import") (part "LED5MM"))
    )
    (comp (ref "LED81")
      (value "BLUE")
      (footprint "eagle-import:LED5MM")
      (libsource (lib "eagle-import") (part "LED5MM"))
    )
    (comp (ref "LED82")
      (value "BLUE")
      (footprint "eagle-import:LED5MM")
      (libsource (lib "eagle-import") (part "LED5MM"))
    )
    (comp (ref "LED83")
      (value "BLUE")
      (footprint "eagle-import:LED5MM")
      (libsource (lib "eagle-import") (part "LED5MM"))
    )
    (comp (ref "LED84")
      (value "BLUE")
      (footprint "eagle-import:LED5MM")
      (libsource (lib "eagle-import") (part "LED5MM"))
    )
    (comp (ref "LED85")
      (value "BLUE")
      (footprint "eagle-import:LED5MM")
      (libsource (lib "eagle-import") (part "LED5MM"))
    )
    (comp (ref "LED86")
      (value "BLUE")
      (footprint "eagle-import:LED5MM")
      (libsource (lib "eagle-import") (part "LED5MM"))
    )
    (comp (ref "LED87")
      (value "BLUE")
      (footprint "eagle-import:LED5MM")
      (libsource (lib "eagle-import") (part "LED5MM"))
    )
    (comp (ref "R74")
      (value "220")
      (footprint "eagle-import:0207_10")
      (libsource (lib "eagle-import") (part "R-EU_0207/10"))
    )
    (comp (ref "R75")
      (value "220")
      (footprint "eagle-import:0207_10")
      (libsource (lib "eagle-import") (part "R-EU_0207/10"))
    )
    (comp (ref "R76")
      (value "220")
      (footprint "eagle-import:0207_10")
      (libsource (lib "eagle-import") (part "R-EU_0207/10"))
    )
    (comp (ref "R77")
      (value "1k")
      (footprint "eagle-import:0207_10")
      (libsource (lib "eagle-import") (part "R-EU_0207/10"))
    )
    (comp (ref "R78")
      (value "220")
      (footprint "eagle-import:0207_10")
      (libsource (lib "eagle-import") (part "R-EU_0207/10"))
    )
    (comp (ref "R79")
      (value "220")
      (footprint "eagle-import:0207_10")
      (libsource (lib "eagle-import") (part "R-EU_0207/10"))
    )
    (comp (ref "R80")
      (value "220")
      (footprint "eagle-import:0207_10")
      (libsource (lib "eagle-import") (part "R-EU_0207/10"))
    )
    (comp (ref "R81")
      (value "220")
      (footprint "eagle-import:0207_10")
      (libsource (lib "eagle-import") (part "R-EU_0207/10"))
    )
    (comp (ref "R82")
      (value "220")
      (footprint "eagle-import:0207_10")
      (libsource (lib "eagle-import") (part "R-EU_0207/10"))
    )
    (comp (ref "R83")
      (value "220")
      (footprint "eagle-import:0207_10")
      (libsource (lib "eagle-import") (part "R-EU_0207/10"))
    )
    (comp (ref "R84")
      (value "220")
      (footprint "eagle-import:0207_10")
      (libsource (lib "eagle-import") (part "R-EU_0207/10"))
    )
    (comp (ref "R85")
      (value "220")
      (footprint "eagle-import:0207_10")
      (libsource (lib "eagle-import") (part "R-EU_0207/10"))
    )
    (comp (ref "R86")
      (value "220")
      (footprint "eagle-import:0207_10")
      (libsource (lib "eagle-import") (part "R-EU_0207/10"))
    )
    (comp (ref "R87")
      (value "220")
      (footprint "eagle-import:0207_10")
      (libsource (lib "eagle-import") (part "R-EU_0207/10"))
    )
    (comp (ref "R88")
      (value "220")
      (footprint "eagle-import:0207_10")
      (libsource (lib "eagle-import") (part "R-EU_0207/10"))
    )
    (comp (ref "R89")
      (value "220")
      (footprint "eagle-import:0207_10")
      (libsource (lib "eagle-import") (part "R-EU_0207/10"))
    )
    (comp (ref "R90")
      (value "220")
      (footprint "eagle-import:0207_10")
      (libsource (lib "eagle-import") (part "R-EU_0207/10"))
    )
    (comp (ref "R91")
      (value "220")
      (footprint "eagle-import:0207_10")
      (libsource (lib "eagle-import") (part "R-EU_0207/10"))
    )
    (comp (ref "R92")
      (value "220")
      (footprint "eagle-import:0207_10")
      (libsource (lib "eagle-import") (part "R-EU_0207/10"))
    )
    (comp (ref "R93")
      (value "220")
      (footprint "eagle-import:0207_10")
      (libsource (lib "eagle-import") (part "R-EU_0207/10"))
    )
    (comp (ref "R94")
      (value "220")
      (footprint "eagle-import:0207_10")
      (libsource (lib "eagle-import") (part "R-EU_0207/10"))
    )
    (comp (ref "R95")
      (value "220")
      (footprint "eagle-import:0207_10")
      (libsource (lib "eagle-import") (part "R-EU_0207/10"))
    )
    (comp (ref "R96")
      (value "220")
      (footprint "eagle-import:0207_10")
      (libsource (lib "eagle-import") (part "R-EU_0207/10"))
    )
    (comp (ref "R97")
      (value "220")
      (footprint "eagle-import:0207_10")
      (libsource (lib "eagle-import") (part "R-EU_0207/10"))
    )
    (comp (ref "R98")
      (value "220")
      (footprint "eagle-import:0207_10")
      (libsource (lib "eagle-import") (part "R-EU_0207/10"))
    )
    (comp (ref "S7")
      (value "RESET")
      (footprint "eagle-import:B3F-10XX")
      (fields (field (name "MPN") "B3F-1000"))
      (libsource (lib "eagle-import") (part "10-XX"))
    )
    (comp (ref "U1")
      (value "74LS161N")
      (footprint "eagle-import:DIL16")
      (libsource (lib "eagle-import") (part "74161NLS"))
    )
    (comp (ref "JP1")
      (value "PINHD-2X7")
      (footprint "eagle-import:2X07")
      (libsource (lib "eagle-import") (part "PINHD-2X7"))
    )
    (comp (ref "JP6")
      (value "PINHD-2X2")
      (footprint "eagle-import:2X02")
      (libsource (lib "eagle-import") (part "PINHD-2X2"))
    )
    (comp (ref "C5")
      (value "0,1uF")
      (footprint "eagle-import:C025-030X050")
      (libsource (lib "eagle-import") (part "C-EU025-030X050"))
    )
    (comp (ref "IC16")
      (value "74LS173N")
      (footprint "eagle-import:DIL16")
      (libsource (lib "eagle-import") (part "74xx-eu_85_74173NLS"))
    )
    (comp (ref "IC17")
      (value "74LS173N")
      (footprint "eagle-import:DIL16")
      (libsource (lib "eagle-import") (part "74xx-eu_85_74173NLS"))
    )
    (comp (ref "IC18")
      (value "74LS245N")
      (footprint "eagle-import:DIL20")
      (libsource (lib "eagle-import") (part "74245NLS"))
    )
    (comp (ref "JP5")
      (value "PINHD-1X8")
      (footprint "eagle-import:1X08")
      (libsource (lib "eagle-import") (part "PINHD-1X8"))
    )
    (comp (ref "LED16")
      (value "YELLOW")
      (footprint "eagle-import:LED5MM")
      (libsource (lib "eagle-import") (part "LED5MM"))
    )
    (comp (ref "LED17")
      (value "YELLOW")
      (footprint "eagle-import:LED5MM")
      (libsource (lib "eagle-import") (part "LED5MM"))
    )
    (comp (ref "LED18")
      (value "YELLOW")
      (footprint "eagle-import:LED5MM")
      (libsource (lib "eagle-import") (part "LED5MM"))
    )
    (comp (ref "LED19")
      (value "YELLOW")
      (footprint "eagle-import:LED5MM")
      (libsource (lib "eagle-import") (part "LED5MM"))
    )
    (comp (ref "LED20")
      (value "BLUE")
      (footprint "eagle-import:LED5MM")
      (libsource (lib "eagle-import") (part "LED5MM"))
    )
    (comp (ref "LED21")
      (value "BLUE")
      (footprint "eagle-import:LED5MM")
      (libsource (lib "eagle-import") (part "LED5MM"))
    )
    (comp (ref "LED22")
      (value "BLUE")
      (footprint "eagle-import:LED5MM")
      (libsource (lib "eagle-import") (part "LED5MM"))
    )
    (comp (ref "LED23")
      (value "BLUE")
      (footprint "eagle-import:LED5MM")
      (libsource (lib "eagle-import") (part "LED5MM"))
    )
    (comp (ref "R24")
      (value "220")
      (footprint "eagle-import:0207_10")
      (libsource (lib "eagle-import") (part "R-EU_0207/10"))
    )
    (comp (ref "R25")
      (value "220")
      (footprint "eagle-import:0207_10")
      (libsource (lib "eagle-import") (part "R-EU_0207/10"))
    )
    (comp (ref "R26")
      (value "220")
      (footprint "eagle-import:0207_10")
      (libsource (lib "eagle-import") (part "R-EU_0207/10"))
    )
    (comp (ref "R27")
      (value "220")
      (footprint "eagle-import:0207_10")
      (libsource (lib "eagle-import") (part "R-EU_0207/10"))
    )
    (comp (ref "R28")
      (value "220")
      (footprint "eagle-import:0207_10")
      (libsource (lib "eagle-import") (part "R-EU_0207/10"))
    )
    (comp (ref "R29")
      (value "220")
      (footprint "eagle-import:0207_10")
      (libsource (lib "eagle-import") (part "R-EU_0207/10"))
    )
    (comp (ref "R30")
      (value "220")
      (footprint "eagle-import:0207_10")
      (libsource (lib "eagle-import") (part "R-EU_0207/10"))
    )
    (comp (ref "R31")
      (value "220")
      (footprint "eagle-import:0207_10")
      (libsource (lib "eagle-import") (part "R-EU_0207/10"))
    )
  )
  (nets
    (net (code "1") (name "A0") (class "Default")
      (node (ref "IC1") (pin "9") (pinfunction "3Y_9") (pintype "output"))
      (node (ref "LED7") (pin "A") (pinfunction "A_A") (pintype "passive"))
      (node (ref "U$3") (pin "1") (pinfunction "A0_1") (pintype "bidirectional"))
      (node (ref "U$4") (pin "1") (pinfunction "A0_1") (pintype "bidirectional"))
    )
    (net (code "2") (name "A1") (class "Default")
      (node (ref "IC1") (pin "12") (pinfunction "4Y_12") (pintype "output"))
      (node (ref "LED6") (pin "A") (pinfunction "A_A") (pintype "passive"))
      (node (ref "U$3") (pin "15") (pinfunction "A1_15") (pintype "bidirectional"))
      (node (ref "U$4") (pin "15") (pinfunction "A1_15") (pintype "bidirectional"))
    )
    (net (code "3") (name "A2") (class "Default")
      (node (ref "IC1") (pin "7") (pinfunction "2Y_7") (pintype "output"))
      (node (ref "LED5") (pin "A") (pinfunction "A_A") (pintype "passive"))
      (node (ref "U$3") (pin "14") (pinfunction "A2_14") (pintype "bidirectional"))
      (node (ref "U$4") (pin "14") (pinfunction "A2_14") (pintype "bidirectional"))
    )
    (net (code "4") (name "A3") (class "Default")
      (node (ref "IC1") (pin "4") (pinfunction "1Y_4") (pintype "output"))
      (node (ref "LED4") (pin "A") (pinfunction "A_A") (pintype "passive"))
      (node (ref "U$3") (pin "13") (pinfunction "A3_13") (pintype "bidirectional"))
      (node (ref "U$4") (pin "13") (pinfunction "A3_13") (pintype "bidirectional"))
    )
    (net (code "5") (name "CE") (class "Default")
      (node (ref "IC27") (pin "13") (pinfunction "D3_13") (pintype "tri_state"))
      (node (ref "JP1") (pin "1") (pinfunction "1_1") (pintype "passive"))
      (node (ref "LED84") (pin "A") (pinfunction "A_A") (pintype "passive"))
    )
    (net (code "6") (name "CF") (class "Default")
      (node (ref "IC26") (pin "23") (pinfunction "A8_23") (pintype "input"))
      (node (ref "IC27") (pin "23") (pinfunction "A8_23") (pintype "input"))
      (node (ref "JP1") (pin "5") (pinfunction "5_5") (pintype "passive"))
    )
    (net (code "7") (name "CLK") (class "Default")
      (node (ref "C4") (pin "1") (pinfunction "1_1") (pintype "passive"))
      (node (ref "IC10") (pin "8") (pinfunction "O_8") (pintype "output"))
      (node (ref "IC12") (pin "1") (pinfunction "I_1") (pintype "input"))
      (node (ref "IC16") (pin "7") (pinfunction "CLK_7") (pintype "input"))
      (node (ref "IC17") (pin "7") (pinfunction "CLK_7") (pintype "input"))
      (node (ref "IC2") (pin "7") (pinfunction "CLK_7") (pintype "input"))
      (node (ref "JP1") (pin "2") (pinfunction "2_2") (pintype "passive"))
      (node (ref "LED2") (pin "A") (pinfunction "A_A") (pintype "passive"))
    )
    (net (code "8") (name "CLR") (class "Default")
      (node (ref "IC16") (pin "15") (pinfunction "CLR_15") (pintype "input"))
      (node (ref "IC17") (pin "15") (pinfunction "CLR_15") (pintype "input"))
      (node (ref "IC2") (pin "15") (pinfunction "CLR_15") (pintype "input"))
      (node (ref "IC40") (pin "8") (pinfunction "O_8") (pintype "output"))
    )
    (net (code "9") (name "GND") (class "Default")
      (node (ref "C1") (pin "2") (pinfunction "2_2") (pintype "passive"))
      (node (ref "C10") (pin "2") (pinfunction "2_2") (pintype "passive"))
      (node (ref "C11") (pin "2") (pinfunction "2_2") (pintype "passive"))
      (node (ref "C12") (pin "2") (pinfunction "2_2") (pintype "passive"))
      (node (ref "C13") (pin "2") (pinfunction "2_2") (pintype "passive"))
      (node (ref "C14") (pin "2") (pinfunction "2_2") (pintype "passive"))
      (node (ref "C15") (pin "2") (pinfunction "2_2") (pintype "passive"))
      (node (ref "C2") (pin "2") (pinfunction "2_2") (pintype "passive"))
      (node (ref "C20") (pin "2") (pinfunction "2_2") (pintype "passive"))
      (node (ref "C3") (pin "2") (pinfunction "2_2") (pintype "passive"))
      (node (ref "C5") (pin "2") (pinfunction "2_2") (pintype "passive"))
      (node (ref "C8") (pin "-") (pinfunction "-_-") (pintype "passive"))
      (node (ref "C9") (pin "2") (pinfunction "2_2") (pintype "passive"))
      (node (ref "IC1") (pin "15") (pinfunction "G_15") (pintype "input"))
      (node (ref "IC10") (pin "7") (pinfunction "GND_7") (pintype "power_in"))
      (node (ref "IC11") (pin "7") (pinfunction "GND_7") (pintype "power_in"))
      (node (ref "IC12") (pin "7") (pinfunction "GND_7") (pintype "power_in"))
      (node (ref "IC14") (pin "15") (pinfunction "G_15") (pintype "input"))
      (node (ref "IC16") (pin "1") (pinfunction "M_1") (pintype "input"))
      (node (ref "IC16") (pin "2") (pinfunction "N_2") (pintype "input"))
      (node (ref "IC17") (pin "1") (pinfunction "M_1") (pintype "input"))
      (node (ref "IC17") (pin "2") (pinfunction "N_2") (pintype "input"))
      (node (ref "IC18") (pin "2") (pinfunction "A1_2") (pintype "bidirectional"))
      (node (ref "IC18") (pin "3") (pinfunction "A2_3") (pintype "bidirectional"))
      (node (ref "IC18") (pin "4") (pinfunction "A3_4") (pintype "bidirectional"))
      (node (ref "IC18") (pin "5") (pinfunction "A4_5") (pintype "bidirectional"))
      (node (ref "IC2") (pin "1") (pinfunction "M_1") (pintype "input"))
      (node (ref "IC2") (pin "2") (pinfunction "N_2") (pintype "input"))
      (node (ref "IC25") (pin "4") (pinfunction "G2A_4") (pintype "input"))
      (node (ref "IC25") (pin "5") (pinfunction "G2B_5") (pintype "input"))
      (node (ref "IC26") (pin "1") (pinfunction "A7_1") (pintype "input"))
      (node (ref "IC26") (pin "12") (pinfunction "GND_12") (pintype "power_in"))
      (node (ref "IC26") (pin "18") (pinfunction "~{CE}_18") (pintype "input"))
      (node (ref "IC26") (pin "19") (pinfunction "A10_19") (pintype "input"))
      (node (ref "IC26") (pin "20") (pinfunction "~{OE}_20") (pintype "input"))
      (node (ref "IC27") (pin "12") (pinfunction "GND_12") (pintype "power_in"))
      (node (ref "IC27") (pin "18") (pinfunction "~{CE}_18") (pintype "input"))
      (node (ref "IC27") (pin "19") (pinfunction "A10_19") (pintype "input"))
      (node (ref "IC27") (pin "20") (pinfunction "~{OE}_20") (pintype "input"))
      (node (ref "IC3") (pin "15") (pinfunction "G_15") (pintype "input"))
      (node (ref "IC4") (pin "15") (pinfunction "G_15") (pintype "input"))
      (node (ref "IC6") (pin "1") (pinfunction "GND_1") (pintype "power_in"))
      (node (ref "IC8") (pin "1") (pinfunction "GND_1") (pintype "power_in"))
      (node (ref "IC8") (pin "6") (pinfunction "THR_6") (pintype "input"))
      (node (ref "IC9") (pin "1") (pinfunction "GND_1") (pintype "power_in"))
      (node (ref "JP6") (pin "3") (pinfunction "3_3") (pintype "passive"))
      (node (ref "JP6") (pin "4") (pinfunction "4_4") (pintype "passive"))
      (node (ref "R10") (pin "1") (pinfunction "1_1") (pintype "passive"))
      (node (ref "R11") (pin "1") (pinfunction "1_1") (pintype "passive"))
      (node (ref "R12") (pin "1") (pinfunction "1_1") (pintype "passive"))
      (node (ref "R13") (pin "1") (pinfunction "1_1") (pintype "passive"))
      (node (ref "R14") (pin "1") (pinfunction "1_1") (pintype "passive"))
      (node (ref "R16") (pin "2") (pinfunction "2_2") (pintype "passive"))
      (node (ref "R17") (pin "1") (pinfunction "1_1") (pintype "passive"))
      (node (ref "R18") (pin "1") (pinfunction "1_1") (pintype "passive"))
      (node (ref "R19") (pin "1") (pinfunction "1_1") (pintype "passive"))
      (node (ref "R20") (pin "1") (pinfunction "1_1") (pintype "passive"))
      (node (ref "R21") (pin "1") (pinfunction "1_1") (pintype "passive"))
      (node (ref "R22") (pin "1") (pinfunction "1_1") (pintype "passive"))
      (node (ref "R23") (pin "1") (pinfunction "1_1") (pintype "passive"))
      (node (ref "R24") (pin "1") (pinfunction "1_1") (pintype "passive"))
      (node (ref "R25") (pin "1") (pinfunction "1_1") (pintype "passive"))
      (node (ref "R26") (pin "1") (pinfunction "1_1") (pintype "passive"))
      (node (ref "R27") (pin "1") (pinfunction "1_1") (pintype "passive"))
      (node (ref "R28") (pin "1") (pinfunction "1_1") (pintype "passive"))
      (node (ref "R29") (pin "1") (pinfunction "1_1") (pintype "passive"))
      (node (ref "R30") (pin "1") (pinfunction "1_1") (pintype "passive"))
      (node (ref "R31") (pin "1") (pinfunction "1_1") (pintype "passive"))
      (node (ref "R74") (pin "1") (pinfunction "1_1") (pintype "passive"))
      (node (ref "R75") (pin "1") (pinfunction "1_1") (pintype "passive"))
      (node (ref "R76") (pin "1") (pinfunction "1_1") (pintype "passive"))
      (node (ref "R77") (pin "2") (pinfunction "2_2") (pintype "passive"))
      (node (ref "R78") (pin "1") (pinfunction "1_1") (pintype "passive"))
      (node (ref "R79") (pin "1") (pinfunction "1_1") (pintype "passive"))
      (node (ref "R80") (pin "1") (pinfunction "1_1") (pintype "passive"))
      (node (ref "R81") (pin "1") (pinfunction "1_1") (pintype "passive"))
      (node (ref "R82") (pin "1") (pinfunction "1_1") (pintype "passive"))
      (node (ref "R83") (pin "1") (pinfunction "1_1") (pintype "passive"))
      (node (ref "R84") (pin "1") (pinfunction "1_1") (pintype "passive"))
      (node (ref "R85") (pin "1") (pinfunction "1_1") (pintype "passive"))
      (node (ref "R86") (pin "1") (pinfunction "1_1") (pintype "passive"))
      (node (ref "R87") (pin "1") (pinfunction "1_1") (pintype "passive"))
      (node (ref "R88") (pin "1") (pinfunction "1_1") (pintype "passive"))
      (node (ref "R89") (pin "1") (pinfunction "1_1") (pintype "passive"))
      (node (ref "R9") (pin "1") (pinfunction "1_1") (pintype "passive"))
      (node (ref "R90") (pin "1") (pinfunction "1_1") (pintype "passive"))
      (node (ref "R91") (pin "1") (pinfunction "1_1") (pintype "passive"))
      (node (ref "R92") (pin "1") (pinfunction "1_1") (pintype "passive"))
      (node (ref "R93") (pin "1") (pinfunction "1_1") (pintype "passive"))
      (node (ref "S1") (pin "2") (pinfunction "P_2") (pintype "passive"))
      (node (ref "S2") (pin "2") (pinfunction "P_2") (pintype "passive"))
      (node (ref "S3") (pin "3") (pinfunction "P_3") (pintype "passive"))
      (node (ref "S4") (pin "2") (pinfunction "P_2") (pintype "passive"))
      (node (ref "SW2") (pin "3") (pinfunction "3_3") (pintype "passive"))
      (node (ref "SW2") (pin "4") (pinfunction "4_4") (pintype "passive"))
      (node (ref "SW2") (pin "7") (pinfunction "7_7") (pintype "passive"))
      (node (ref "SW2") (pin "8") (pinfunction "8_8") (pintype "passive"))
      (node (ref "SW3") (pin "11") (pinfunction "11_11") (pintype "passive"))
      (node (ref "SW3") (pin "12") (pinfunction "12_12") (pintype "passive"))
      (node (ref "SW3") (pin "15") (pinfunction "15_15") (pintype "passive"))
      (node (ref "SW3") (pin "16") (pinfunction "16_16") (pintype "passive"))
      (node (ref "SW3") (pin "3") (pinfunction "3_3") (pintype "passive"))
      (node (ref "SW3") (pin "4") (pinfunction "4_4") (pintype "passive"))
      (node (ref "SW3") (pin "7") (pinfunction "7_7") (pintype "passive"))
      (node (ref "SW3") (pin "8") (pinfunction "8_8") (pintype "passive"))
      (node (ref "U$3") (pin "2") (pinfunction "CS_2") (pintype "bidirectional"))
      (node (ref "U$3") (pin "8") (pinfunction "GND_8") (pintype "bidirectional"))
      (node (ref "U$4") (pin "2") (pinfunction "CS_2") (pintype "bidirectional"))
      (node (ref "U$4") (pin "8") (pinfunction "GND_8") (pintype "bidirectional"))
    )
    (net (code "10") (name "HLT") (class "Default")
      (node (ref "IC12") (pin "5") (pinfunction "I_5") (pintype "input"))
      (node (ref "IC26") (pin "17") (pinfunction "D7_17") (pintype "tri_state"))
      (node (ref "LED72") (pin "A") (pinfunction "A_A") (pintype "passive"))
    )
    (net (code "11") (name "IR_4") (class "Default")
      (node (ref "IC17") (pin "6") (pinfunction "Q4_6") (pintype "tri_state"))
      (node (ref "IC26") (pin "5") (pinfunction "A3_5") (pintype "input"))
      (node (ref "IC27") (pin "5") (pinfunction "A3_5") (pintype "input"))
      (node (ref "LED23") (pin "A") (pinfunction "A_A") (pintype "passive"))
    )
    (net (code "12") (name "IR_5") (class "Default")
      (node (ref "IC17") (pin "5") (pinfunction "Q3_5") (pintype "tri_state"))
      (node (ref "IC26") (pin "4") (pinfunction "A4_4") (pintype "input"))
      (node (ref "IC27") (pin "4") (pinfunction "A4_4") (pintype "input"))
      (node (ref "LED22") (pin "A") (pinfunction "A_A") (pintype "passive"))
    )
    (net (code "13") (name "IR_6") (class "Default")
      (node (ref "IC17") (pin "4") (pinfunction "Q2_4") (pintype "tri_state"))
      (node (ref "IC26") (pin "3") (pinfunction "A5_3") (pintype "input"))
      (node (ref "IC27") (pin "3") (pinfunction "A5_3") (pintype "input"))
      (node (ref "LED21") (pin "A") (pinfunction "A_A") (pintype "passive"))
    )
    (net (code "14") (name "IR_7") (class "Default")
      (node (ref "IC17") (pin "3") (pinfunction "Q1_3") (pintype "tri_state"))
      (node (ref "IC26") (pin "2") (pinfunction "A6_2") (pintype "input"))
      (node (ref "IC27") (pin "2") (pinfunction "A6_2") (pintype "input"))
      (node (ref "LED20") (pin "A") (pinfunction "A_A") (pintype "passive"))
    )
    (net (code "15") (name "IR_BUS_0") (class "Default")
      (node (ref "IC16") (pin "11") (pinfunction "D4_11") (pintype "input"))
      (node (ref "IC18") (pin "11") (pinfunction "B8_11") (pintype "bidirectional"))
      (node (ref "JP5") (pin "1") (pinfunction "1_1") (pintype "passive"))
    )
    (net (code "16") (name "IR_BUS_1") (class "Default")
      (node (ref "IC16") (pin "12") (pinfunction "D3_12") (pintype "input"))
      (node (ref "IC18") (pin "12") (pinfunction "B7_12") (pintype "bidirectional"))
      (node (ref "JP5") (pin "2") (pinfunction "2_2") (pintype "passive"))
    )
    (net (code "17") (name "IR_BUS_2") (class "Default")
      (node (ref "IC16") (pin "13") (pinfunction "D2_13") (pintype "input"))
      (node (ref "IC18") (pin "13") (pinfunction "B6_13") (pintype "bidirectional"))
      (node (ref "JP5") (pin "3") (pinfunction "3_3") (pintype "passive"))
    )
    (net (code "18") (name "IR_BUS_3") (class "Default")
      (node (ref "IC16") (pin "14") (pinfunction "D1_14") (pintype "input"))
      (node (ref "IC18") (pin "14") (pinfunction "B5_14") (pintype "bidirectional"))
      (node (ref "JP5") (pin "4") (pinfunction "4_4") (pintype "passive"))
    )
    (net (code "19") (name "IR_BUS_4") (class "Default")
      (node (ref "IC17") (pin "11") (pinfunction "D4_11") (pintype "input"))
      (node (ref "IC18") (pin "15") (pinfunction "B4_15") (pintype "bidirectional"))
      (node (ref "JP5") (pin "5") (pinfunction "5_5") (pintype "passive"))
    )
    (net (code "20") (name "IR_BUS_5") (class "Default")
      (node (ref "IC17") (pin "12") (pinfunction "D3_12") (pintype "input"))
      (node (ref "IC18") (pin "16") (pinfunction "B3_16") (pintype "bidirectional"))
      (node (ref "JP5") (pin "6") (pinfunction "6_6") (pintype "passive"))
    )
    (net (code "21") (name "IR_BUS_6") (class "Default")
      (node (ref "IC17") (pin "13") (pinfunction "D2_13") (pintype "input"))
      (node (ref "IC18") (pin "17") (pinfunction "B2_17") (pintype "bidirectional"))
      (node (ref "JP5") (pin "7") (pinfunction "7_7") (pintype "passive"))
    )
    (net (code "22") (name "IR_BUS_7") (class "Default")
      (node (ref "IC17") (pin "14") (pinfunction "D1_14") (pintype "input"))
      (node (ref "IC18") (pin "18") (pinfunction "B1_18") (pintype "bidirectional"))
      (node (ref "JP5") (pin "8") (pinfunction "8_8") (pintype "passive"))
    )
    (net (code "23") (name "MAR_BUS_0") (class "Default")
      (node (ref "IC2") (pin "11") (pinfunction "D4_11") (pintype "input"))
      (node (ref "JP2") (pin "1") (pinfunction "1_1") (pintype "passive"))
    )
    (net (code "24") (name "MAR_BUS_1") (class "Default")
      (node (ref "IC2") (pin "12") (pinfunction "D3_12") (pintype "input"))
      (node (ref "JP2") (pin "2") (pinfunction "2_2") (pintype "passive"))
    )
    (net (code "25") (name "MAR_BUS_2") (class "Default")
      (node (ref "IC2") (pin "13") (pinfunction "D2_13") (pintype "input"))
      (node (ref "JP2") (pin "3") (pinfunction "3_3") (pintype "passive"))
    )
    (net (code "26") (name "MAR_BUS_3") (class "Default")
      (node (ref "IC2") (pin "14") (pinfunction "D1_14") (pintype "input"))
      (node (ref "JP2") (pin "4") (pinfunction "4_4") (pintype "passive"))
    )
    (net (code "27") (name "N_AI") (class "Default")
      (node (ref "IC28") (pin "10") (pinfunction "O_10") (pintype "output"))
      (node (ref "JP1") (pin "10") (pinfunction "10_10") (pintype "passive"))
    )
    (net (code "28") (name "N_AO") (class "Default")
      (node (ref "IC28") (pin "12") (pinfunction "O_12") (pintype "output"))
      (node (ref "JP1") (pin "11") (pinfunction "11_11") (pintype "passive"))
    )
    (net (code "29") (name "N_BI") (class "Default")
      (node (ref "IC39") (pin "4") (pinfunction "O_4") (pintype "output"))
      (node (ref "JP1") (pin "13") (pinfunction "13_13") (pintype "passive"))
    )
    (net (code "30") (name "N_CLK") (class "Default")
      (node (ref "IC12") (pin "2") (pinfunction "O_2") (pintype "output"))
      (node (ref "U1") (pin "2") (pinfunction "CLK_2") (pintype "input"))
    )
    (net (code "31") (name "N_CLR") (class "Default")
      (node (ref "IC40") (pin "10") (pinfunction "I1_10") (pintype "input"))
      (node (ref "IC40") (pin "11") (pinfunction "O_11") (pintype "output"))
      (node (ref "IC40") (pin "4") (pinfunction "I0_4") (pintype "input"))
      (node (ref "IC40") (pin "9") (pinfunction "I0_9") (pintype "input"))
      (node (ref "JP1") (pin "8") (pinfunction "8_8") (pintype "passive"))
    )
    (net (code "32") (name "N_CO") (class "Default")
      (node (ref "IC39") (pin "6") (pinfunction "O_6") (pintype "output"))
      (node (ref "JP1") (pin "14") (pinfunction "14_14") (pintype "passive"))
    )
    (net (code "33") (name "N_EO") (class "Default")
      (node (ref "IC39") (pin "2") (pinfunction "O_2") (pintype "output"))
      (node (ref "JP1") (pin "12") (pinfunction "12_12") (pintype "passive"))
    )
    (net (code "34") (name "N_FI") (class "Default")
      (node (ref "IC39") (pin "10") (pinfunction "O_10") (pintype "output"))
      (node (ref "JP1") (pin "7") (pinfunction "7_7") (pintype "passive"))
    )
    (net (code "35") (name "N_II") (class "Default")
      (node (ref "IC16") (pin "10") (pinfunction "G2_10") (pintype "input"))
      (node (ref "IC16") (pin "9") (pinfunction "G1_9") (pintype "input"))
      (node (ref "IC17") (pin "10") (pinfunction "G2_10") (pintype "input"))
      (node (ref "IC17") (pin "9") (pinfunction "G1_9") (pintype "input"))
      (node (ref "IC28") (pin "8") (pinfunction "O_8") (pintype "output"))
    )
    (net (code "36") (name "N_IO") (class "Default")
      (node (ref "IC18") (pin "19") (pinfunction "G_19") (pintype "input"))
      (node (ref "IC28") (pin "6") (pinfunction "O_6") (pintype "output"))
    )
    (net (code "37") (name "N_J") (class "Default")
      (node (ref "IC39") (pin "8") (pinfunction "O_8") (pintype "output"))
      (node (ref "JP1") (pin "9") (pinfunction "9_9") (pintype "passive"))
    )
    (net (code "38") (name "N_MI") (class "Default")
      (node (ref "IC2") (pin "10") (pinfunction "G2_10") (pintype "input"))
      (node (ref "IC2") (pin "9") (pinfunction "G1_9") (pintype "input"))
      (node (ref "IC28") (pin "2") (pinfunction "O_2") (pintype "output"))
    )
    (net (code "39") (name "N_RO") (class "Default")
      (node (ref "IC28") (pin "4") (pinfunction "O_4") (pintype "output"))
      (node (ref "IC5") (pin "19") (pinfunction "G_19") (pintype "input"))
    )
    (net (code "40") (name "Net-(IC1A-1A)") (class "Default")
      (node (ref "IC1") (pin "2") (pinfunction "1A_2") (pintype "input"))
      (node (ref "SW2") (pin "5") (pinfunction "5_5") (pintype "passive"))
    )
    (net (code "41") (name "Net-(IC1A-1B)") (class "Default")
      (node (ref "IC1") (pin "3") (pinfunction "1B_3") (pintype "input"))
      (node (ref "IC2") (pin "3") (pinfunction "Q1_3") (pintype "tri_state"))
    )
    (net (code "42") (name "Net-(IC1A-2A)") (class "Default")
      (node (ref "IC1") (pin "5") (pinfunction "2A_5") (pintype "input"))
      (node (ref "SW2") (pin "6") (pinfunction "6_6") (pintype "passive"))
    )
    (net (code "43") (name "Net-(IC1A-2B)") (class "Default")
      (node (ref "IC1") (pin "6") (pinfunction "2B_6") (pintype "input"))
      (node (ref "IC2") (pin "4") (pinfunction "Q2_4") (pintype "tri_state"))
    )
    (net (code "44") (name "Net-(IC1A-3A)") (class "Default")
      (node (ref "IC1") (pin "11") (pinfunction "3A_11") (pintype "input"))
      (node (ref "SW2") (pin "1") (pinfunction "1_1") (pintype "passive"))
    )
    (net (code "45") (name "Net-(IC1A-3B)") (class "Default")
      (node (ref "IC1") (pin "10") (pinfunction "3B_10") (pintype "input"))
      (node (ref "IC2") (pin "6") (pinfunction "Q4_6") (pintype "tri_state"))
    )
    (net (code "46") (name "Net-(IC1A-4A)") (class "Default")
      (node (ref "IC1") (pin "14") (pinfunction "4A_14") (pintype "input"))
      (node (ref "SW2") (pin "2") (pinfunction "2_2") (pintype "passive"))
    )
    (net (code "47") (name "Net-(IC1A-4B)") (class "Default")
      (node (ref "IC1") (pin "13") (pinfunction "4B_13") (pintype "input"))
      (node (ref "IC2") (pin "5") (pinfunction "Q3_5") (pintype "tri_state"))
    )
    (net (code "48") (name "Net-(IC3A-1A)") (class "Default")
      (node (ref "IC3") (pin "2") (pinfunction "1A_2") (pintype "input"))
      (node (ref "SW3") (pin "9") (pinfunction "9_9") (pintype "passive"))
    )
    (net (code "49") (name "Net-(IC3A-1Y)") (class "Default")
      (node (ref "IC3") (pin "4") (pinfunction "1Y_4") (pintype "output"))
      (node (ref "U$3") (pin "4") (pinfunction "D0_4") (pintype "bidirectional"))
    )
    (net (code "50") (name "Net-(IC3A-2A)") (class "Default")
      (node (ref "IC3") (pin "5") (pinfunction "2A_5") (pintype "input"))
      (node (ref "SW3") (pin "10") (pinfunction "10_10") (pintype "passive"))
    )
    (net (code "51") (name "Net-(IC3A-2Y)") (class "Default")
      (node (ref "IC3") (pin "7") (pinfunction "2Y_7") (pintype "output"))
      (node (ref "U$3") (pin "6") (pinfunction "D1_6") (pintype "bidirectional"))
    )
    (net (code "52") (name "Net-(IC3A-3A)") (class "Default")
      (node (ref "IC3") (pin "11") (pinfunction "3A_11") (pintype "input"))
      (node (ref "SW3") (pin "5") (pinfunction "5_5") (pintype "passive"))
    )
    (net (code "53") (name "Net-(IC3A-3Y)") (class "Default")
      (node (ref "IC3") (pin "9") (pinfunction "3Y_9") (pintype "output"))
      (node (ref "U$3") (pin "12") (pinfunction "D3_12") (pintype "bidirectional"))
    )
    (net (code "54") (name "Net-(IC3A-4A)") (class "Default")
      (node (ref "IC3") (pin "14") (pinfunction "4A_14") (pintype "input"))
      (node (ref "SW3") (pin "6") (pinfunction "6_6") (pintype "passive"))
    )
    (net (code "55") (name "Net-(IC3A-4Y)") (class "Default")
      (node (ref "IC3") (pin "12") (pinfunction "4Y_12") (pintype "output"))
      (node (ref "U$3") (pin "10") (pinfunction "D2_10") (pintype "bidirectional"))
    )
    (net (code "56") (name "Net-(IC4A-1A)") (class "Default")
      (node (ref "IC4") (pin "2") (pinfunction "1A_2") (pintype "input"))
      (node (ref "SW3") (pin "13") (pinfunction "13_13") (pintype "passive"))
    )
    (net (code "57") (name "Net-(IC4A-1Y)") (class "Default")
      (node (ref "IC4") (pin "4") (pinfunction "1Y_4") (pintype "output"))
      (node (ref "U$4") (pin "12") (pinfunction "D3_12") (pintype "bidirectional"))
    )
    (net (code "58") (name "Net-(IC4A-2A)") (class "Default")
      (node (ref "IC4") (pin "5") (pinfunction "2A_5") (pintype "input"))
      (node (ref "SW3") (pin "14") (pinfunction "14_14") (pintype "passive"))
    )
    (net (code "59") (name "Net-(IC4A-2Y)") (class "Default")
      (node (ref "IC4") (pin "7") (pinfunction "2Y_7") (pintype "output"))
      (node (ref "U$4") (pin "10") (pinfunction "D2_10") (pintype "bidirectional"))
    )
    (net (code "60") (name "Net-(IC4A-3A)") (class "Default")
      (node (ref "IC4") (pin "11") (pinfunction "3A_11") (pintype "input"))
      (node (ref "SW3") (pin "1") (pinfunction "1_1") (pintype "passive"))
    )
    (net (code "61") (name "Net-(IC4A-3Y)") (class "Default")
      (node (ref "IC4") (pin "9") (pinfunction "3Y_9") (pintype "output"))
      (node (ref "U$4") (pin "4") (pinfunction "D0_4") (pintype "bidirectional"))
    )
    (net (code "62") (name "Net-(IC4A-4A)") (class "Default")
      (node (ref "IC4") (pin "14") (pinfunction "4A_14") (pintype "input"))
      (node (ref "SW3") (pin "2") (pinfunction "2_2") (pintype "passive"))
    )
    (net (code "63") (name "Net-(IC4A-4Y)") (class "Default")
      (node (ref "IC4") (pin "12") (pinfunction "4Y_12") (pintype "output"))
      (node (ref "U$4") (pin "6") (pinfunction "D1_6") (pintype "bidirectional"))
    )
    (net (code "64") (name "Net-(IC5A-A1)") (class "Default")
      (node (ref "IC5") (pin "2") (pinfunction "A1_2") (pintype "bidirectional"))
      (node (ref "IC7") (pin "2") (pinfunction "O_2") (pintype "output"))
      (node (ref "LED14") (pin "A") (pinfunction "A_A") (pintype "passive"))
    )
    (net (code "65") (name "Net-(IC5A-A2)") (class "Default")
      (node (ref "IC5") (pin "3") (pinfunction "A2_3") (pintype "bidirectional"))
      (node (ref "IC7") (pin "4") (pinfunction "O_4") (pintype "output"))
      (node (ref "LED15") (pin "A") (pinfunction "A_A") (pintype "passive"))
    )
    (net (code "66") (name "Net-(IC5A-A3)") (class "Default")
      (node (ref "IC5") (pin "4") (pinfunction "A3_4") (pintype "bidirectional"))
      (node (ref "IC7") (pin "6") (pinfunction "O_6") (pintype "output"))
      (node (ref "LED12") (pin "A") (pinfunction "A_A") (pintype "passive"))
    )
    (net (code "67") (name "Net-(IC5A-A4)") (class "Default")
      (node (ref "IC5") (pin "5") (pinfunction "A4_5") (pintype "bidirectional"))
      (node (ref "IC7") (pin "8") (pinfunction "O_8") (pintype "output"))
      (node (ref "LED13") (pin "A") (pinfunction "A_A") (pintype "passive"))
    )
    (net (code "68") (name "Net-(IC5A-A5)") (class "Default")
      (node (ref "IC5") (pin "6") (pinfunction "A5_6") (pintype "bidirectional"))
      (node (ref "IC7") (pin "10") (pinfunction "O_10") (pintype "output"))
      (node (ref "LED10") (pin "A") (pinfunction "A_A") (pintype "passive"))
    )
    (net (code "69") (name "Net-(IC5A-A6)") (class "Default")
      (node (ref "IC5") (pin "7") (pinfunction "A6_7") (pintype "bidirectional"))
      (node (ref "IC7") (pin "12") (pinfunction "O_12") (pintype "output"))
      (node (ref "LED11") (pin "A") (pinfunction "A_A") (pintype "passive"))
    )
    (net (code "70") (name "Net-(IC6-CV)") (class "Default")
      (node (ref "C12") (pin "1") (pinfunction "1_1") (pintype "passive"))
      (node (ref "IC6") (pin "5") (pinfunction "CV_5") (pintype "input"))
    )
    (net (code "71") (name "Net-(IC6-DIS)") (class "Default")
      (node (ref "C13") (pin "1") (pinfunction "1_1") (pintype "passive"))
      (node (ref "IC6") (pin "6") (pinfunction "THR_6") (pintype "input"))
      (node (ref "IC6") (pin "7") (pinfunction "DIS_7") (pintype "input"))
      (node (ref "R7") (pin "2") (pinfunction "2_2") (pintype "passive"))
    )
    (net (code "72") (name "Net-(IC6-TR)") (class "Default")
      (node (ref "IC6") (pin "2") (pinfunction "TR_2") (pintype "input"))
      (node (ref "R5") (pin "2") (pinfunction "2_2") (pintype "passive"))
      (node (ref "S3") (pin "1") (pinfunction "S_1") (pintype "passive"))
    )
    (net (code "73") (name "Net-(IC7A-I)") (class "Default")
      (node (ref "IC7") (pin "1") (pinfunction "I_1") (pintype "input"))
      (node (ref "U$3") (pin "5") (pinfunction "O0_5") (pintype "bidirectional"))
    )
    (net (code "74") (name "Net-(IC7B-I)") (class "Default")
      (node (ref "IC7") (pin "3") (pinfunction "I_3") (pintype "input"))
      (node (ref "U$3") (pin "7") (pinfunction "O1_7") (pintype "bidirectional"))
    )
    (net (code "75") (name "Net-(IC7C-I)") (class "Default")
      (node (ref "IC7") (pin "5") (pinfunction "I_5") (pintype "input"))
      (node (ref "U$3") (pin "9") (pinfunction "O2_9") (pintype "bidirectional"))
    )
    (net (code "76") (name "Net-(IC7D-I)") (class "Default")
      (node (ref "IC7") (pin "9") (pinfunction "I_9") (pintype "input"))
      (node (ref "U$3") (pin "11") (pinfunction "O3_11") (pintype "bidirectional"))
    )
    (net (code "77") (name "Net-(IC7E-I)") (class "Default")
      (node (ref "IC7") (pin "11") (pinfunction "I_11") (pintype "input"))
      (node (ref "U$4") (pin "11") (pinfunction "O3_11") (pintype "bidirectional"))
    )
    (net (code "78") (name "Net-(IC7F-I)") (class "Default")
      (node (ref "IC7") (pin "13") (pinfunction "I_13") (pintype "input"))
      (node (ref "U$4") (pin "9") (pinfunction "O2_9") (pintype "bidirectional"))
    )
    (net (code "79") (name "Net-(IC8-CV)") (class "Default")
      (node (ref "C14") (pin "1") (pinfunction "1_1") (pintype "passive"))
      (node (ref "IC8") (pin "5") (pinfunction "CV_5") (pintype "input"))
    )
    (net (code "80") (name "Net-(IC8-R)") (class "Default")
      (node (ref "IC8") (pin "4") (pinfunction "R_4") (pintype "input"))
      (node (ref "R8") (pin "2") (pinfunction "2_2") (pintype "passive"))
      (node (ref "S4") (pin "3") (pinfunction "S_3") (pintype "passive"))
    )
    (net (code "81") (name "Net-(IC8-TR)") (class "Default")
      (node (ref "IC8") (pin "2") (pinfunction "TR_2") (pintype "input"))
      (node (ref "R15") (pin "2") (pinfunction "2_2") (pintype "passive"))
      (node (ref "S4") (pin "1") (pinfunction "O_1") (pintype "passive"))
    )
    (net (code "82") (name "Net-(IC9-CV)") (class "Default")
      (node (ref "C11") (pin "1") (pinfunction "1_1") (pintype "passive"))
      (node (ref "IC9") (pin "5") (pinfunction "CV_5") (pintype "input"))
    )
    (net (code "83") (name "Net-(IC9-DIS)") (class "Default")
      (node (ref "IC9") (pin "7") (pinfunction "DIS_7") (pintype "input"))
      (node (ref "R2") (pin "1") (pinfunction "1_1") (pintype "passive"))
      (node (ref "R3") (pin "1") (pinfunction "1_1") (pintype "passive"))
    )
    (net (code "84") (name "Net-(IC9-THR)") (class "Default")
      (node (ref "C8") (pin "+") (pinfunction "+_+") (pintype "passive"))
      (node (ref "IC9") (pin "2") (pinfunction "TR_2") (pintype "input"))
      (node (ref "IC9") (pin "6") (pinfunction "THR_6") (pintype "input"))
      (node (ref "R1") (pin "E") (pinfunction "VSS_E") (pintype "passive"))
    )
    (net (code "85") (name "Net-(IC10A-I0)") (class "Default")
      (node (ref "IC10") (pin "1") (pinfunction "I0_1") (pintype "input"))
      (node (ref "IC9") (pin "3") (pinfunction "Q_3") (pintype "output"))
    )
    (net (code "86") (name "Net-(IC10A-I1)") (class "Default")
      (node (ref "IC10") (pin "2") (pinfunction "I1_2") (pintype "input"))
      (node (ref "IC12") (pin "3") (pinfunction "I_3") (pintype "input"))
      (node (ref "IC8") (pin "3") (pinfunction "Q_3") (pintype "output"))
    )
    (net (code "87") (name "Net-(IC10A-O)") (class "Default")
      (node (ref "IC10") (pin "3") (pinfunction "O_3") (pintype "output"))
      (node (ref "IC11") (pin "1") (pinfunction "I0_1") (pintype "input"))
    )
    (net (code "88") (name "Net-(IC10B-I0)") (class "Default")
      (node (ref "IC10") (pin "4") (pinfunction "I0_4") (pintype "input"))
      (node (ref "IC12") (pin "4") (pinfunction "O_4") (pintype "output"))
    )
    (net (code "89") (name "Net-(IC10B-I1)") (class "Default")
      (node (ref "IC10") (pin "5") (pinfunction "I1_5") (pintype "input"))
      (node (ref "IC6") (pin "3") (pinfunction "Q_3") (pintype "output"))
    )
    (net (code "90") (name "Net-(IC10B-O)") (class "Default")
      (node (ref "IC10") (pin "6") (pinfunction "O_6") (pintype "output"))
      (node (ref "IC11") (pin "2") (pinfunction "I1_2") (pintype "input"))
    )
    (net (code "91") (name "Net-(IC10C-I0)") (class "Default")
      (node (ref "IC10") (pin "9") (pinfunction "I0_9") (pintype "input"))
      (node (ref "IC11") (pin "3") (pinfunction "O_3") (pintype "output"))
    )
    (net (code "92") (name "Net-(IC10C-I1)") (class "Default")
      (node (ref "IC10") (pin "10") (pinfunction "I1_10") (pintype "input"))
      (node (ref "IC12") (pin "6") (pinfunction "O_6") (pintype "output"))
    )
    (net (code "93") (name "Net-(IC13A-I)") (class "Default")
      (node (ref "IC13") (pin "1") (pinfunction "I_1") (pintype "input"))
      (node (ref "U$4") (pin "7") (pinfunction "O1_7") (pintype "bidirectional"))
    )
    (net (code "94") (name "Net-(IC13A-O)") (class "Default")
      (node (ref "IC13") (pin "2") (pinfunction "O_2") (pintype "output"))
      (node (ref "IC5") (pin "8") (pinfunction "A7_8") (pintype "bidirectional"))
      (node (ref "LED8") (pin "A") (pinfunction "A_A") (pintype "passive"))
    )
    (net (code "95") (name "Net-(IC13B-I)") (class "Default")
      (node (ref "IC13") (pin "3") (pinfunction "I_3") (pintype "input"))
      (node (ref "U$4") (pin "5") (pinfunction "O0_5") (pintype "bidirectional"))
    )
    (net (code "96") (name "Net-(IC13B-O)") (class "Default")
      (node (ref "IC13") (pin "4") (pinfunction "O_4") (pintype "output"))
      (node (ref "IC5") (pin "9") (pinfunction "A8_9") (pintype "bidirectional"))
      (node (ref "LED9") (pin "A") (pinfunction "A_A") (pintype "passive"))
    )
    (net (code "97") (name "Net-(IC14A-4A)") (class "Default")
      (node (ref "IC14") (pin "14") (pinfunction "4A_14") (pintype "input"))
      (node (ref "S1") (pin "3") (pinfunction "S_3") (pintype "passive"))
    )
    (net (code "98") (name "Net-(IC14A-4B)") (class "Default")
      (node (ref "IC14") (pin "13") (pinfunction "4B_13") (pintype "input"))
      (node (ref "IC15") (pin "3") (pinfunction "O_3") (pintype "output"))
    )
    (net (code "99") (name "Net-(IC14A-4Y)") (class "Default")
      (node (ref "IC14") (pin "12") (pinfunction "4Y_12") (pintype "output"))
      (node (ref "U$3") (pin "3") (pinfunction "WE_3") (pintype "bidirectional"))
      (node (ref "U$4") (pin "3") (pinfunction "WE_3") (pintype "bidirectional"))
    )
    (net (code "100") (name "Net-(IC15A-I0)") (class "Default")
      (node (ref "C4") (pin "2") (pinfunction "2_2") (pintype "passive"))
      (node (ref "IC15") (pin "1") (pinfunction "I0_1") (pintype "input"))
      (node (ref "R23") (pin "2") (pinfunction "2_2") (pintype "passive"))
    )
    (net (code "101") (name "Net-(IC16A-Q1)") (class "Default")
      (node (ref "IC16") (pin "3") (pinfunction "Q1_3") (pintype "tri_state"))
      (node (ref "IC18") (pin "6") (pinfunction "A5_6") (pintype "bidirectional"))
      (node (ref "LED16") (pin "A") (pinfunction "A_A") (pintype "passive"))
    )
    (net (code "102") (name "Net-(IC16A-Q2)") (class "Default")
      (node (ref "IC16") (pin "4") (pinfunction "Q2_4") (pintype "tri_state"))
      (node (ref "IC18") (pin "7") (pinfunction "A6_7") (pintype "bidirectional"))
      (node (ref "LED17") (pin "A") (pinfunction "A_A") (pintype "passive"))
    )
    (net (code "103") (name "Net-(IC16A-Q3)") (class "Default")
      (node (ref "IC16") (pin "5") (pinfunction "Q3_5") (pintype "tri_state"))
      (node (ref "IC18") (pin "8") (pinfunction "A7_8") (pintype "bidirectional"))
      (node (ref "LED18") (pin "A") (pinfunction "A_A") (pintype "passive"))
    )
    (net (code "104") (name "Net-(IC16A-Q4)") (class "Default")
      (node (ref "IC16") (pin "6") (pinfunction "Q4_6") (pintype "tri_state"))
      (node (ref "IC18") (pin "9") (pinfunction "A8_9") (pintype "bidirectional"))
      (node (ref "LED19") (pin "A") (pinfunction "A_A") (pintype "passive"))
    )
    (net (code "105") (name "Net-(IC25A-A)") (class "Default")
      (node (ref "IC25") (pin "1") (pinfunction "A_1") (pintype "input"))
      (node (ref "IC26") (pin "8") (pinfunction "A0_8") (pintype "input"))
      (node (ref "IC27") (pin "8") (pinfunction "A0_8") (pintype "input"))
      (node (ref "LED66") (pin "A") (pinfunction "A_A") (pintype "passive"))
      (node (ref "U1") (pin "14") (pinfunction "QA_14") (pintype "output"))
    )
    (net (code "106") (name "Net-(IC25A-B)") (class "Default")
      (node (ref "IC25") (pin "2") (pinfunction "B_2") (pintype "input"))
      (node (ref "IC26") (pin "7") (pinfunction "A1_7") (pintype "input"))
      (node (ref "IC27") (pin "7") (pinfunction "A1_7") (pintype "input"))
      (node (ref "LED65") (pin "A") (pinfunction "A_A") (pintype "passive"))
      (node (ref "U1") (pin "13") (pinfunction "QB_13") (pintype "output"))
    )
    (net (code "107") (name "Net-(IC25A-C)") (class "Default")
      (node (ref "IC25") (pin "3") (pinfunction "C_3") (pintype "input"))
      (node (ref "IC26") (pin "6") (pinfunction "A2_6") (pintype "input"))
      (node (ref "IC27") (pin "6") (pinfunction "A2_6") (pintype "input"))
      (node (ref "LED64") (pin "A") (pinfunction "A_A") (pintype "passive"))
      (node (ref "U1") (pin "12") (pinfunction "QC_12") (pintype "output"))
    )
    (net (code "108") (name "Net-(IC25A-Y0)") (class "Default")
      (node (ref "IC25") (pin "15") (pinfunction "Y0_15") (pintype "output"))
      (node (ref "LED71") (pin "K") (pinfunction "C_K") (pintype "passive"))
    )
    (net (code "109") (name "Net-(IC25A-Y1)") (class "Default")
      (node (ref "IC25") (pin "14") (pinfunction "Y1_14") (pintype "output"))
      (node (ref "LED70") (pin "K") (pinfunction "C_K") (pintype "passive"))
    )
    (net (code "110") (name "Net-(IC25A-Y2)") (class "Default")
      (node (ref "IC25") (pin "13") (pinfunction "Y2_13") (pintype "output"))
      (node (ref "LED69") (pin "K") (pinfunction "C_K") (pintype "passive"))
    )
    (net (code "111") (name "Net-(IC25A-Y3)") (class "Default")
      (node (ref "IC25") (pin "12") (pinfunction "Y3_12") (pintype "output"))
      (node (ref "LED68") (pin "K") (pinfunction "C_K") (pintype "passive"))
    )
    (net (code "112") (name "Net-(IC25A-Y4)") (class "Default")
      (node (ref "IC25") (pin "11") (pinfunction "Y4_11") (pintype "output"))
      (node (ref "LED67") (pin "K") (pinfunction "C_K") (pintype "passive"))
    )
    (net (code "113") (name "Net-(IC25A-Y5)") (class "Default")
      (node (ref "IC25") (pin "10") (pinfunction "Y5_10") (pintype "output"))
      (node (ref "IC40") (pin "5") (pinfunction "I1_5") (pintype "input"))
    )
    (net (code "114") (name "Net-(IC26-D0)") (class "Default")
      (node (ref "IC26") (pin "9") (pinfunction "D0_9") (pintype "tri_state"))
      (node (ref "IC28") (pin "13") (pinfunction "I_13") (pintype "input"))
      (node (ref "LED79") (pin "A") (pinfunction "A_A") (pintype "passive"))
    )
    (net (code "115") (name "Net-(IC26-D1)") (class "Default")
      (node (ref "IC26") (pin "10") (pinfunction "D1_10") (pintype "tri_state"))
      (node (ref "IC28") (pin "11") (pinfunction "I_11") (pintype "input"))
      (node (ref "LED78") (pin "A") (pinfunction "A_A") (pintype "passive"))
    )
    (net (code "116") (name "Net-(IC26-D2)") (class "Default")
      (node (ref "IC26") (pin "11") (pinfunction "D2_11") (pintype "tri_state"))
      (node (ref "IC28") (pin "9") (pinfunction "I_9") (pintype "input"))
      (node (ref "LED77") (pin "A") (pinfunction "A_A") (pintype "passive"))
    )
    (net (code "117") (name "Net-(IC26-D3)") (class "Default")
      (node (ref "IC26") (pin "13") (pinfunction "D3_13") (pintype "tri_state"))
      (node (ref "IC28") (pin "5") (pinfunction "I_5") (pintype "input"))
      (node (ref "LED76") (pin "A") (pinfunction "A_A") (pintype "passive"))
    )
    (net (code "118") (name "Net-(IC26-D4)") (class "Default")
      (node (ref "IC26") (pin "14") (pinfunction "D4_14") (pintype "tri_state"))
      (node (ref "IC28") (pin "3") (pinfunction "I_3") (pintype "input"))
      (node (ref "LED75") (pin "A") (pinfunction "A_A") (pintype "passive"))
    )
    (net (code "119") (name "Net-(IC26-D6)") (class "Default")
      (node (ref "IC26") (pin "16") (pinfunction "D6_16") (pintype "tri_state"))
      (node (ref "IC28") (pin "1") (pinfunction "I_1") (pintype "input"))
      (node (ref "LED73") (pin "A") (pinfunction "A_A") (pintype "passive"))
    )
    (net (code "120") (name "Net-(IC27-D0)") (class "Default")
      (node (ref "IC27") (pin "9") (pinfunction "D0_9") (pintype "tri_state"))
      (node (ref "IC39") (pin "11") (pinfunction "I_11") (pintype "input"))
      (node (ref "LED87") (pin "A") (pinfunction "A_A") (pintype "passive"))
    )
    (net (code "121") (name "Net-(IC27-D1)") (class "Default")
      (node (ref "IC27") (pin "10") (pinfunction "D1_10") (pintype "tri_state"))
      (node (ref "IC39") (pin "9") (pinfunction "I_9") (pintype "input"))
      (node (ref "LED86") (pin "A") (pinfunction "A_A") (pintype "passive"))
    )
    (net (code "122") (name "Net-(IC27-D2)") (class "Default")
      (node (ref "IC27") (pin "11") (pinfunction "D2_11") (pintype "tri_state"))
      (node (ref "IC39") (pin "5") (pinfunction "I_5") (pintype "input"))
      (node (ref "LED85") (pin "A") (pinfunction "A_A") (pintype "passive"))
    )
    (net (code "123") (name "Net-(IC27-D5)") (class "Default")
      (node (ref "IC27") (pin "15") (pinfunction "D5_15") (pintype "tri_state"))
      (node (ref "IC39") (pin "3") (pinfunction "I_3") (pintype "input"))
      (node (ref "LED82") (pin "A") (pinfunction "A_A") (pintype "passive"))
    )
    (net (code "124") (name "Net-(IC27-D7)") (class "Default")
      (node (ref "IC27") (pin "17") (pinfunction "D7_17") (pintype "tri_state"))
      (node (ref "IC39") (pin "1") (pinfunction "I_1") (pintype "input"))
      (node (ref "LED80") (pin "A") (pinfunction "A_A") (pintype "passive"))
    )
    (net (code "125") (name "Net-(IC40A-I0)") (class "Default")
      (node (ref "IC40") (pin "1") (pinfunction "I0_1") (pintype "input"))
      (node (ref "IC40") (pin "2") (pinfunction "I1_2") (pintype "input"))
      (node (ref "IC40") (pin "6") (pinfunction "O_6") (pintype "output"))
    )
    (net (code "126") (name "Net-(IC40A-O)") (class "Default")
      (node (ref "IC40") (pin "3") (pinfunction "O_3") (pintype "output"))
      (node (ref "U1") (pin "1") (pinfunction "CLR_1") (pintype "input"))
    )
    (net (code "127") (name "Net-(IC40D-I0)") (class "Default")
      (node (ref "IC40") (pin "12") (pinfunction "I0_12") (pintype "input"))
      (node (ref "IC40") (pin "13") (pinfunction "I1_13") (pintype "input"))
      (node (ref "R77") (pin "1") (pinfunction "1_1") (pintype "passive"))
      (node (ref "S7") (pin "1") (pinfunction "S_1") (pintype "passive"))
    )
    (net (code "128") (name "Net-(LED1-PadA)") (class "Default")
      (node (ref "LED1") (pin "A") (pinfunction "A_A") (pintype "passive"))
      (node (ref "R6") (pin "2") (pinfunction "2_2") (pintype "passive"))
    )
    (net (code "129") (name "Net-(LED2-C)") (class "Default")
      (node (ref "LED2") (pin "K") (pinfunction "C_K") (pintype "passive"))
      (node (ref "R16") (pin "1") (pinfunction "1_1") (pintype "passive"))
    )
    (net (code "130") (name "Net-(LED3-C)") (class "Default")
      (node (ref "LED3") (pin "K") (pinfunction "C_K") (pintype "passive"))
      (node (ref "S2") (pin "3") (pinfunction "S_3") (pintype "passive"))
    )
    (net (code "131") (name "Net-(LED3-PadA)") (class "Default")
      (node (ref "LED3") (pin "A") (pinfunction "A_A") (pintype "passive"))
      (node (ref "R4") (pin "2") (pinfunction "2_2") (pintype "passive"))
    )
    (net (code "132") (name "Net-(LED4-C)") (class "Default")
      (node (ref "LED4") (pin "K") (pinfunction "C_K") (pintype "passive"))
      (node (ref "R12") (pin "2") (pinfunction "2_2") (pintype "passive"))
    )
    (net (code "133") (name "Net-(LED5-C)") (class "Default")
      (node (ref "LED5") (pin "K") (pinfunction "C_K") (pintype "passive"))
      (node (ref "R11") (pin "2") (pinfunction "2_2") (pintype "passive"))
    )
    (net (code "134") (name "Net-(LED6-C)") (class "Default")
      (node (ref "LED6") (pin "K") (pinfunction "C_K") (pintype "passive"))
      (node (ref "R10") (pin "2") (pinfunction "2_2") (pintype "passive"))
    )
    (net (code "135") (name "Net-(LED7-C)") (class "Default")
      (node (ref "LED7") (pin "K") (pinfunction "C_K") (pintype "passive"))
      (node (ref "R9") (pin "2") (pinfunction "2_2") (pintype "passive"))
    )
    (net (code "136") (name "Net-(LED8-C)") (class "Default")
      (node (ref "LED8") (pin "K") (pinfunction "C_K") (pintype "passive"))
      (node (ref "R13") (pin "2") (pinfunction "2_2") (pintype "passive"))
    )
    (net (code "137") (name "Net-(LED9-C)") (class "Default")
      (node (ref "LED9") (pin "K") (pinfunction "C_K") (pintype "passive"))
      (node (ref "R14") (pin "2") (pinfunction "2_2") (pintype "passive"))
    )
    (net (code "138") (name "Net-(LED10-C)") (class "Default")
      (node (ref "LED10") (pin "K") (pinfunction "C_K") (pintype "passive"))
      (node (ref "R17") (pin "2") (pinfunction "2_2") (pintype "passive"))
    )
    (net (code "139") (name "Net-(LED11-C)") (class "Default")
      (node (ref "LED11") (pin "K") (pinfunction "C_K") (pintype "passive"))
      (node (ref "R18") (pin "2") (pinfunction "2_2") (pintype "passive"))
    )
    (net (code "140") (name "Net-(LED12-C)") (class "Default")
      (node (ref "LED12") (pin "K") (pinfunction "C_K") (pintype "passive"))
      (node (ref "R19") (pin "2") (pinfunction "2_2") (pintype "passive"))
    )
    (net (code "141") (name "Net-(LED13-C)") (class "Default")
      (node (ref "LED13") (pin "K") (pinfunction "C_K") (pintype "passive"))
      (node (ref "R20") (pin "2") (pinfunction "2_2") (pintype "passive"))
    )
    (net (code "142") (name "Net-(LED14-C)") (class "Default")
      (node (ref "LED14") (pin "K") (pinfunction "C_K") (pintype "passive"))
      (node (ref "R21") (pin "2") (pinfunction "2_2") (pintype "passive"))
    )
    (net (code "143") (name "Net-(LED15-C)") (class "Default")
      (node (ref "LED15") (pin "K") (pinfunction "C_K") (pintype "passive"))
      (node (ref "R22") (pin "2") (pinfunction "2_2") (pintype "passive"))
    )
    (net (code "144") (name "Net-(LED16-C)") (class "Default")
      (node (ref "LED16") (pin "K") (pinfunction "C_K") (pintype "passive"))
      (node (ref "R27") (pin "2") (pinfunction "2_2") (pintype "passive"))
    )
    (net (code "145") (name "Net-(LED17-C)") (class "Default")
      (node (ref "LED17") (pin "K") (pinfunction "C_K") (pintype "passive"))
      (node (ref "R26") (pin "2") (pinfunction "2_2") (pintype "passive"))
    )
    (net (code "146") (name "Net-(LED18-C)") (class "Default")
      (node (ref "LED18") (pin "K") (pinfunction "C_K") (pintype "passive"))
      (node (ref "R25") (pin "2") (pinfunction "2_2") (pintype "passive"))
    )
    (net (code "147") (name "Net-(LED19-C)") (class "Default")
      (node (ref "LED19") (pin "K") (pinfunction "C_K") (pintype "passive"))
      (node (ref "R24") (pin "2") (pinfunction "2_2") (pintype "passive"))
    )
    (net (code "148") (name "Net-(LED20-C)") (class "Default")
      (node (ref "LED20") (pin "K") (pinfunction "C_K") (pintype "passive"))
      (node (ref "R31") (pin "2") (pinfunction "2_2") (pintype "passive"))
    )
    (net (code "149") (name "Net-(LED21-C)") (class "Default")
      (node (ref "LED21") (pin "K") (pinfunction "C_K") (pintype "passive"))
      (node (ref "R30") (pin "2") (pinfunction "2_2") (pintype "passive"))
    )
    (net (code "150") (name "Net-(LED22-C)") (class "Default")
      (node (ref "LED22") (pin "K") (pinfunction "C_K") (pintype "passive"))
      (node (ref "R29") (pin "2") (pinfunction "2_2") (pintype "passive"))
    )
    (net (code "151") (name "Net-(LED23-C)") (class "Default")
      (node (ref "LED23") (pin "K") (pinfunction "C_K") (pintype "passive"))
      (node (ref "R28") (pin "2") (pinfunction "2_2") (pintype "passive"))
    )
    (net (code "152") (name "Net-(LED64-C)") (class "Default")
      (node (ref "LED64") (pin "K") (pinfunction "C_K") (pintype "passive"))
      (node (ref "R74") (pin "2") (pinfunction "2_2") (pintype "passive"))
    )
    (net (code "153") (name "Net-(LED65-C)") (class "Default")
      (node (ref "LED65") (pin "K") (pinfunction "C_K") (pintype "passive"))
      (node (ref "R75") (pin "2") (pinfunction "2_2") (pintype "passive"))
    )
    (net (code "154") (name "Net-(LED66-C)") (class "Default")
      (node (ref "LED66") (pin "K") (pinfunction "C_K") (pintype "passive"))
      (node (ref "R76") (pin "2") (pinfunction "2_2") (pintype "passive"))
    )
    (net (code "155") (name "Net-(LED67-PadA)") (class "Default")
      (node (ref "LED67") (pin "A") (pinfunction "A_A") (pintype "passive"))
      (node (ref "R98") (pin "1") (pinfunction "1_1") (pintype "passive"))
    )
    (net (code "156") (name "Net-(LED68-PadA)") (class "Default")
      (node (ref "LED68") (pin "A") (pinfunction "A_A") (pintype "passive"))
      (node (ref "R94") (pin "1") (pinfunction "1_1") (pintype "passive"))
    )
    (net (code "157") (name "Net-(LED69-PadA)") (class "Default")
      (node (ref "LED69") (pin "A") (pinfunction "A_A") (pintype "passive"))
      (node (ref "R95") (pin "1") (pinfunction "1_1") (pintype "passive"))
    )
    (net (code "158") (name "Net-(LED70-PadA)") (class "Default")
      (node (ref "LED70") (pin "A") (pinfunction "A_A") (pintype "passive"))
      (node (ref "R96") (pin "1") (pinfunction "1_1") (pintype "passive"))
    )
    (net (code "159") (name "Net-(LED71-PadA)") (class "Default")
      (node (ref "LED71") (pin "A") (pinfunction "A_A") (pintype "passive"))
      (node (ref "R97") (pin "1") (pinfunction "1_1") (pintype "passive"))
    )
    (net (code "160") (name "Net-(LED72-C)") (class "Default")
      (node (ref "LED72") (pin "K") (pinfunction "C_K") (pintype "passive"))
      (node (ref "R93") (pin "2") (pinfunction "2_2") (pintype "passive"))
    )
    (net (code "161") (name "Net-(LED73-C)") (class "Default")
      (node (ref "LED73") (pin "K") (pinfunction "C_K") (pintype "passive"))
      (node (ref "R92") (pin "2") (pinfunction "2_2") (pintype "passive"))
    )
    (net (code "162") (name "Net-(LED74-C)") (class "Default")
      (node (ref "LED74") (pin "K") (pinfunction "C_K") (pintype "passive"))
      (node (ref "R91") (pin "2") (pinfunction "2_2") (pintype "passive"))
    )
    (net (code "163") (name "Net-(LED75-C)") (class "Default")
      (node (ref "LED75") (pin "K") (pinfunction "C_K") (pintype "passive"))
      (node (ref "R90") (pin "2") (pinfunction "2_2") (pintype "passive"))
    )
    (net (code "164") (name "Net-(LED76-C)") (class "Default")
      (node (ref "LED76") (pin "K") (pinfunction "C_K") (pintype "passive"))
      (node (ref "R89") (pin "2") (pinfunction "2_2") (pintype "passive"))
    )
    (net (code "165") (name "Net-(LED77-C)") (class "Default")
      (node (ref "LED77") (pin "K") (pinfunction "C_K") (pintype "passive"))
      (node (ref "R88") (pin "2") (pinfunction "2_2") (pintype "passive"))
    )
    (net (code "166") (name "Net-(LED78-C)") (class "Default")
      (node (ref "LED78") (pin "K") (pinfunction "C_K") (pintype "passive"))
      (node (ref "R87") (pin "2") (pinfunction "2_2") (pintype "passive"))
    )
    (net (code "167") (name "Net-(LED79-C)") (class "Default")
      (node (ref "LED79") (pin "K") (pinfunction "C_K") (pintype "passive"))
      (node (ref "R86") (pin "2") (pinfunction "2_2") (pintype "passive"))
    )
    (net (code "168") (name "Net-(LED80-C)") (class "Default")
      (node (ref "LED80") (pin "K") (pinfunction "C_K") (pintype "passive"))
      (node (ref "R85") (pin "2") (pinfunction "2_2") (pintype "passive"))
    )
    (net (code "169") (name "Net-(LED81-C)") (class "Default")
      (node (ref "LED81") (pin "K") (pinfunction "C_K") (pintype "passive"))
      (node (ref "R84") (pin "2") (pinfunction "2_2") (pintype "passive"))
    )
    (net (code "170") (name "Net-(LED82-C)") (class "Default")
      (node (ref "LED82") (pin "K") (pinfunction "C_K") (pintype "passive"))
      (node (ref "R83") (pin "2") (pinfunction "2_2") (pintype "passive"))
    )
    (net (code "171") (name "Net-(LED83-C)") (class "Default")
      (node (ref "LED83") (pin "K") (pinfunction "C_K") (pintype "passive"))
      (node (ref "R78") (pin "2") (pinfunction "2_2") (pintype "passive"))
    )
    (net (code "172") (name "Net-(LED84-C)") (class "Default")
      (node (ref "LED84") (pin "K") (pinfunction "C_K") (pintype "passive"))
      (node (ref "R79") (pin "2") (pinfunction "2_2") (pintype "passive"))
    )
    (net (code "173") (name "Net-(LED85-C)") (class "Default")
      (node (ref "LED85") (pin "K") (pinfunction "C_K") (pintype "passive"))
      (node (ref "R80") (pin "2") (pinfunction "2_2") (pintype "passive"))
    )
    (net (code "174") (name "Net-(LED86-C)") (class "Default")
      (node (ref "LED86") (pin "K") (pinfunction "C_K") (pintype "passive"))
      (node (ref "R81") (pin "2") (pinfunction "2_2") (pintype "passive"))
    )
    (net (code "175") (name "Net-(LED87-C)") (class "Default")
      (node (ref "LED87") (pin "K") (pinfunction "C_K") (pintype "passive"))
      (node (ref "R82") (pin "2") (pinfunction "2_2") (pintype "passive"))
    )
    (net (code "176") (name "Net-(R1-OUT)") (class "Default")
      (node (ref "R1") (pin "S") (pinfunction "OUT_S") (pintype "passive"))
      (node (ref "R3") (pin "2") (pinfunction "2_2") (pintype "passive"))
    )
    (net (code "177") (name "OI") (class "Default")
      (node (ref "IC27") (pin "14") (pinfunction "D4_14") (pintype "tri_state"))
      (node (ref "JP1") (pin "4") (pinfunction "4_4") (pintype "passive"))
      (node (ref "LED83") (pin "A") (pinfunction "A_A") (pintype "passive"))
    )
    (net (code "178") (name "PROG") (class "Default")
      (node (ref "IC1") (pin "1") (pinfunction "~{A}/B_1") (pintype "input"))
      (node (ref "IC14") (pin "1") (pinfunction "~{A}/B_1") (pintype "input"))
      (node (ref "IC3") (pin "1") (pinfunction "~{A}/B_1") (pintype "input"))
      (node (ref "IC4") (pin "1") (pinfunction "~{A}/B_1") (pintype "input"))
      (node (ref "LED1") (pin "K") (pinfunction "C_K") (pintype "passive"))
      (node (ref "S2") (pin "1") (pinfunction "O_1") (pintype "passive"))
    )
    (net (code "179") (name "RAM_BUS_0") (class "Default")
      (node (ref "IC4") (pin "10") (pinfunction "3B_10") (pintype "input"))
      (node (ref "IC5") (pin "11") (pinfunction "B8_11") (pintype "bidirectional"))
      (node (ref "JP3") (pin "1") (pinfunction "1_1") (pintype "passive"))
    )
    (net (code "180") (name "RAM_BUS_1") (class "Default")
      (node (ref "IC4") (pin "13") (pinfunction "4B_13") (pintype "input"))
      (node (ref "IC5") (pin "12") (pinfunction "B7_12") (pintype "bidirectional"))
      (node (ref "JP3") (pin "2") (pinfunction "2_2") (pintype "passive"))
    )
    (net (code "181") (name "RAM_BUS_2") (class "Default")
      (node (ref "IC4") (pin "6") (pinfunction "2B_6") (pintype "input"))
      (node (ref "IC5") (pin "13") (pinfunction "B6_13") (pintype "bidirectional"))
      (node (ref "JP3") (pin "3") (pinfunction "3_3") (pintype "passive"))
    )
    (net (code "182") (name "RAM_BUS_3") (class "Default")
      (node (ref "IC4") (pin "3") (pinfunction "1B_3") (pintype "input"))
      (node (ref "IC5") (pin "14") (pinfunction "B5_14") (pintype "bidirectional"))
      (node (ref "JP3") (pin "4") (pinfunction "4_4") (pintype "passive"))
    )
    (net (code "183") (name "RAM_BUS_4") (class "Default")
      (node (ref "IC3") (pin "10") (pinfunction "3B_10") (pintype "input"))
      (node (ref "IC5") (pin "15") (pinfunction "B4_15") (pintype "bidirectional"))
      (node (ref "JP3") (pin "5") (pinfunction "5_5") (pintype "passive"))
    )
    (net (code "184") (name "RAM_BUS_5") (class "Default")
      (node (ref "IC3") (pin "13") (pinfunction "4B_13") (pintype "input"))
      (node (ref "IC5") (pin "16") (pinfunction "B3_16") (pintype "bidirectional"))
      (node (ref "JP3") (pin "6") (pinfunction "6_6") (pintype "passive"))
    )
    (net (code "185") (name "RAM_BUS_6") (class "Default")
      (node (ref "IC3") (pin "6") (pinfunction "2B_6") (pintype "input"))
      (node (ref "IC5") (pin "17") (pinfunction "B2_17") (pintype "bidirectional"))
      (node (ref "JP3") (pin "7") (pinfunction "7_7") (pintype "passive"))
    )
    (net (code "186") (name "RAM_BUS_7") (class "Default")
      (node (ref "IC3") (pin "3") (pinfunction "1B_3") (pintype "input"))
      (node (ref "IC5") (pin "18") (pinfunction "B1_18") (pintype "bidirectional"))
      (node (ref "JP3") (pin "8") (pinfunction "8_8") (pintype "passive"))
    )
    (net (code "187") (name "RI") (class "Default")
      (node (ref "IC15") (pin "2") (pinfunction "I1_2") (pintype "input"))
      (node (ref "IC26") (pin "15") (pinfunction "D5_15") (pintype "tri_state"))
      (node (ref "LED74") (pin "A") (pinfunction "A_A") (pintype "passive"))
    )
    (net (code "188") (name "SU") (class "Default")
      (node (ref "IC27") (pin "16") (pinfunction "D6_16") (pintype "tri_state"))
      (node (ref "JP1") (pin "3") (pinfunction "3_3") (pintype "passive"))
      (node (ref "LED81") (pin "A") (pinfunction "A_A") (pintype "passive"))
    )
    (net (code "189") (name "VCC") (class "Default")
      (node (ref "C1") (pin "1") (pinfunction "1_1") (pintype "passive"))
      (node (ref "C10") (pin "1") (pinfunction "1_1") (pintype "passive"))
      (node (ref "C15") (pin "1") (pinfunction "1_1") (pintype "passive"))
      (node (ref "C2") (pin "1") (pinfunction "1_1") (pintype "passive"))
      (node (ref "C20") (pin "1") (pinfunction "1_1") (pintype "passive"))
      (node (ref "C3") (pin "1") (pinfunction "1_1") (pintype "passive"))
      (node (ref "C5") (pin "1") (pinfunction "1_1") (pintype "passive"))
      (node (ref "C9") (pin "1") (pinfunction "1_1") (pintype "passive"))
      (node (ref "IC10") (pin "14") (pinfunction "VCC_14") (pintype "power_in"))
      (node (ref "IC11") (pin "14") (pinfunction "VCC_14") (pintype "power_in"))
      (node (ref "IC12") (pin "14") (pinfunction "VCC_14") (pintype "power_in"))
      (node (ref "IC18") (pin "1") (pinfunction "DIR_1") (pintype "input"))
      (node (ref "IC25") (pin "6") (pinfunction "G1_6") (pintype "input"))
      (node (ref "IC26") (pin "21") (pinfunction "~{WE}_21") (pintype "input"))
      (node (ref "IC26") (pin "24") (pinfunction "VCC_24") (pintype "power_in"))
      (node (ref "IC27") (pin "1") (pinfunction "A7_1") (pintype "input"))
      (node (ref "IC27") (pin "21") (pinfunction "~{WE}_21") (pintype "input"))
      (node (ref "IC27") (pin "24") (pinfunction "VCC_24") (pintype "power_in"))
      (node (ref "IC5") (pin "1") (pinfunction "DIR_1") (pintype "input"))
      (node (ref "IC6") (pin "4") (pinfunction "R_4") (pintype "input"))
      (node (ref "IC6") (pin "8") (pinfunction "V+_8") (pintype "power_in"))
      (node (ref "IC8") (pin "8") (pinfunction "V+_8") (pintype "power_in"))
      (node (ref "IC9") (pin "4") (pinfunction "R_4") (pintype "input"))
      (node (ref "IC9") (pin "8") (pinfunction "V+_8") (pintype "power_in"))
      (node (ref "JP6") (pin "1") (pinfunction "1_1") (pintype "passive"))
      (node (ref "JP6") (pin "2") (pinfunction "2_2") (pintype "passive"))
      (node (ref "R15") (pin "1") (pinfunction "1_1") (pintype "passive"))
      (node (ref "R2") (pin "2") (pinfunction "2_2") (pintype "passive"))
      (node (ref "R4") (pin "1") (pinfunction "1_1") (pintype "passive"))
      (node (ref "R5") (pin "1") (pinfunction "1_1") (pintype "passive"))
      (node (ref "R6") (pin "1") (pinfunction "1_1") (pintype "passive"))
      (node (ref "R7") (pin "1") (pinfunction "1_1") (pintype "passive"))
      (node (ref "R8") (pin "1") (pinfunction "1_1") (pintype "passive"))
      (node (ref "R94") (pin "2") (pinfunction "2_2") (pintype "passive"))
      (node (ref "R95") (pin "2") (pinfunction "2_2") (pintype "passive"))
      (node (ref "R96") (pin "2") (pinfunction "2_2") (pintype "passive"))
      (node (ref "R97") (pin "2") (pinfunction "2_2") (pintype "passive"))
      (node (ref "R98") (pin "2") (pinfunction "2_2") (pintype "passive"))
      (node (ref "S7") (pin "3") (pinfunction "P_3") (pintype "passive"))
      (node (ref "U$3") (pin "16") (pinfunction "VCC_16") (pintype "bidirectional"))
      (node (ref "U$4") (pin "16") (pinfunction "VCC_16") (pintype "bidirectional"))
      (node (ref "U1") (pin "10") (pinfunction "ENT_10") (pintype "input"))
      (node (ref "U1") (pin "7") (pinfunction "ENP_7") (pintype "input"))
      (node (ref "U1") (pin "9") (pinfunction "LD_9") (pintype "input"))
    )
    (net (code "190") (name "ZF") (class "Default")
      (node (ref "IC26") (pin "22") (pinfunction "A9_22") (pintype "input"))
      (node (ref "IC27") (pin "22") (pinfunction "A9_22") (pintype "input"))
      (node (ref "JP1") (pin "6") (pinfunction "6_6") (pintype "passive"))
    )
    (net (code "191") (name "unconnected-(IC8-DIS-Pad7)") (class "Default")
      (node (ref "IC8") (pin "7") (pinfunction "DIS_7") (pintype "input"))
    )
    (net (code "192") (name "unconnected-(IC14A-1A-Pad2)") (class "Default")
      (node (ref "IC14") (pin "2") (pinfunction "1A_2") (pintype "input"))
    )
    (net (code "193") (name "unconnected-(IC14A-1B-Pad3)") (class "Default")
      (node (ref "IC14") (pin "3") (pinfunction "1B_3") (pintype "input"))
    )
    (net (code "194") (name "unconnected-(IC14A-1Y-Pad4)") (class "Default")
      (node (ref "IC14") (pin "4") (pinfunction "1Y_4") (pintype "output"))
    )
    (net (code "195") (name "unconnected-(IC14A-2A-Pad5)") (class "Default")
      (node (ref "IC14") (pin "5") (pinfunction "2A_5") (pintype "input"))
    )
    (net (code "196") (name "unconnected-(IC14A-2B-Pad6)") (class "Default")
      (node (ref "IC14") (pin "6") (pinfunction "2B_6") (pintype "input"))
    )
    (net (code "197") (name "unconnected-(IC14A-2Y-Pad7)") (class "Default")
      (node (ref "IC14") (pin "7") (pinfunction "2Y_7") (pintype "output"))
    )
    (net (code "198") (name "unconnected-(IC14A-3A-Pad11)") (class "Default")
      (node (ref "IC14") (pin "11") (pinfunction "3A_11") (pintype "input"))
    )
    (net (code "199") (name "unconnected-(IC14A-3B-Pad10)") (class "Default")
      (node (ref "IC14") (pin "10") (pinfunction "3B_10") (pintype "input"))
    )
    (net (code "200") (name "unconnected-(IC14A-3Y-Pad9)") (class "Default")
      (node (ref "IC14") (pin "9") (pinfunction "3Y_9") (pintype "output"))
    )
    (net (code "201") (name "unconnected-(IC25A-Y6-Pad9)") (class "Default")
      (node (ref "IC25") (pin "9") (pinfunction "Y6_9") (pintype "output"))
    )
    (net (code "202") (name "unconnected-(IC25A-Y7-Pad7)") (class "Default")
      (node (ref "IC25") (pin "7") (pinfunction "Y7_7") (pintype "output"))
    )
    (net (code "203") (name "unconnected-(IC39F-I-Pad13)") (class "Default")
      (node (ref "IC39") (pin "13") (pinfunction "I_13") (pintype "input"))
    )
    (net (code "204") (name "unconnected-(IC39F-O-Pad12)") (class "Default")
      (node (ref "IC39") (pin "12") (pinfunction "O_12") (pintype "output"))
    )
    (net (code "205") (name "unconnected-(R1-VDD-PadA)") (class "Default")
      (node (ref "R1") (pin "A") (pinfunction "VDD_A") (pintype "passive"))
    )
    (net (code "206") (name "unconnected-(S1-O-Pad1)") (class "Default")
      (node (ref "S1") (pin "1") (pinfunction "O_1") (pintype "passive"))
    )
    (net (code "207") (name "unconnected-(S3-P1-Pad4)") (class "Default")
      (node (ref "S3") (pin "4") (pinfunction "P1_4") (pintype "passive"))
    )
    (net (code "208") (name "unconnected-(S3-S1-Pad2)") (class "Default")
      (node (ref "S3") (pin "2") (pinfunction "S1_2") (pintype "passive"))
    )
    (net (code "209") (name "unconnected-(S7-P1-Pad4)") (class "Default")
      (node (ref "S7") (pin "4") (pinfunction "P1_4") (pintype "passive"))
    )
    (net (code "210") (name "unconnected-(S7-S1-Pad2)") (class "Default")
      (node (ref "S7") (pin "2") (pinfunction "S1_2") (pintype "passive"))
    )
    (net (code "211") (name "unconnected-(U1A-A-Pad3)") (class "Default")
      (node (ref "U1") (pin "3") (pinfunction "A_3") (pintype "input"))
    )
    (net (code "212") (name "unconnected-(U1A-B-Pad4)") (class "Default")
      (node (ref "U1") (pin "4") (pinfunction "B_4") (pintype "input"))
    )
    (net (code "213") (name "unconnected-(U1A-C-Pad5)") (class "Default")
      (node (ref "U1") (pin "5") (pinfunction "C_5") (pintype "input"))
    )
    (net (code "214") (name "unconnected-(U1A-D-Pad6)") (class "Default")
      (node (ref "U1") (pin "6") (pinfunction "D_6") (pintype "input"))
    )
    (net (code "215") (name "unconnected-(U1A-QD-Pad11)") (class "Default")
      (node (ref "U1") (pin "11") (pinfunction "QD_11") (pintype "output"))
    )
    (net (code "216") (name "unconnected-(U1A-RCO-Pad15)") (class "Default")
      (node (ref "U1") (pin "15") (pinfunction "RCO_15") (pintype "output"))
    )
  )
)
